# eit_passive_filter.net
KiCad netlist of a schematic drawn in EAGLE
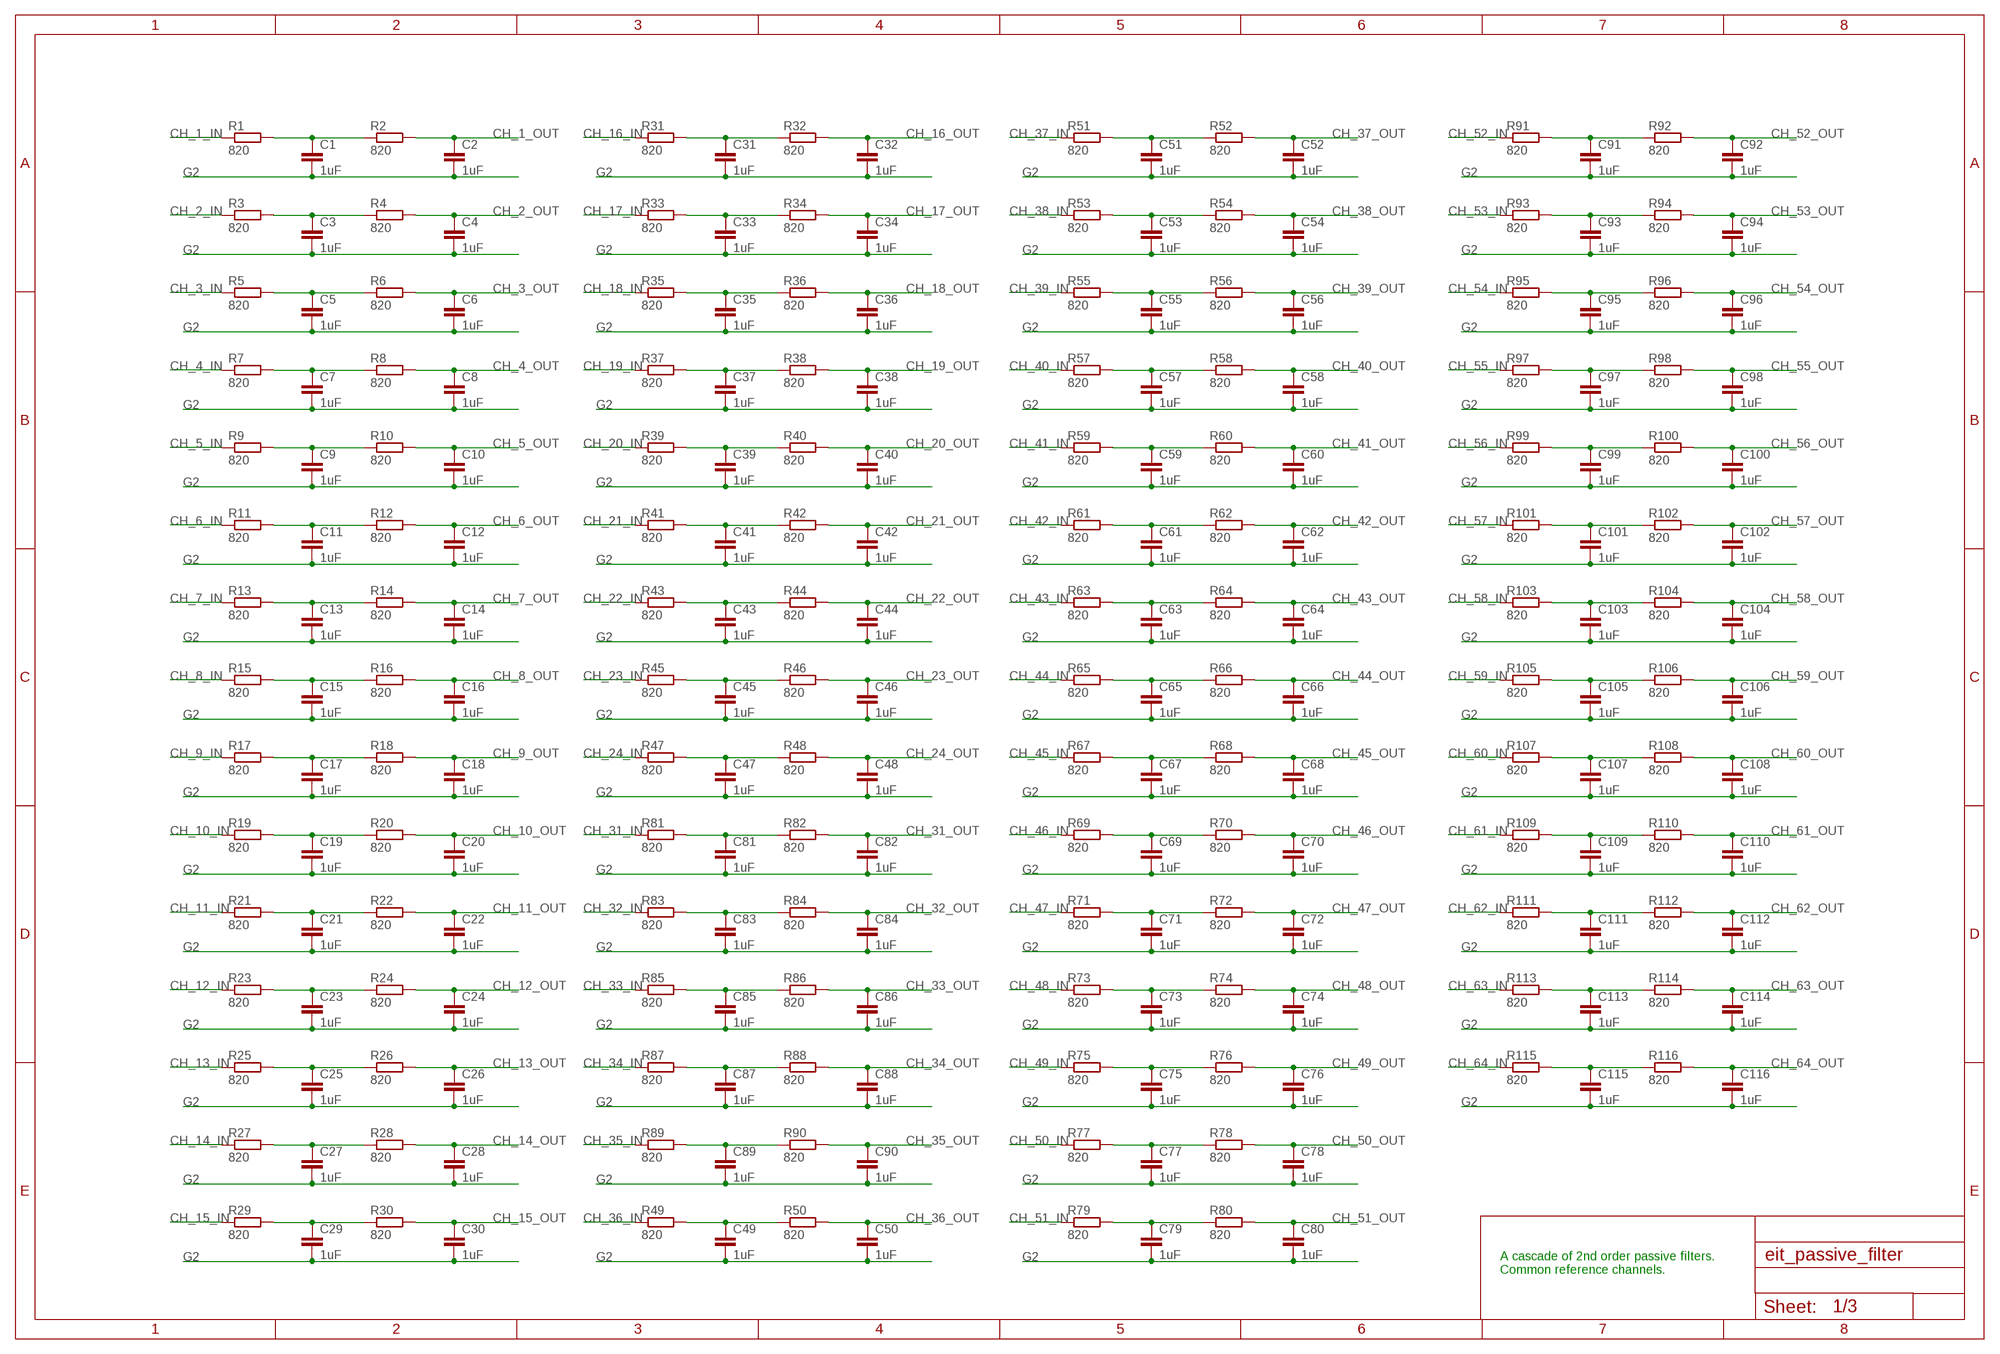
[diagram p0: schematic, sheet 1]
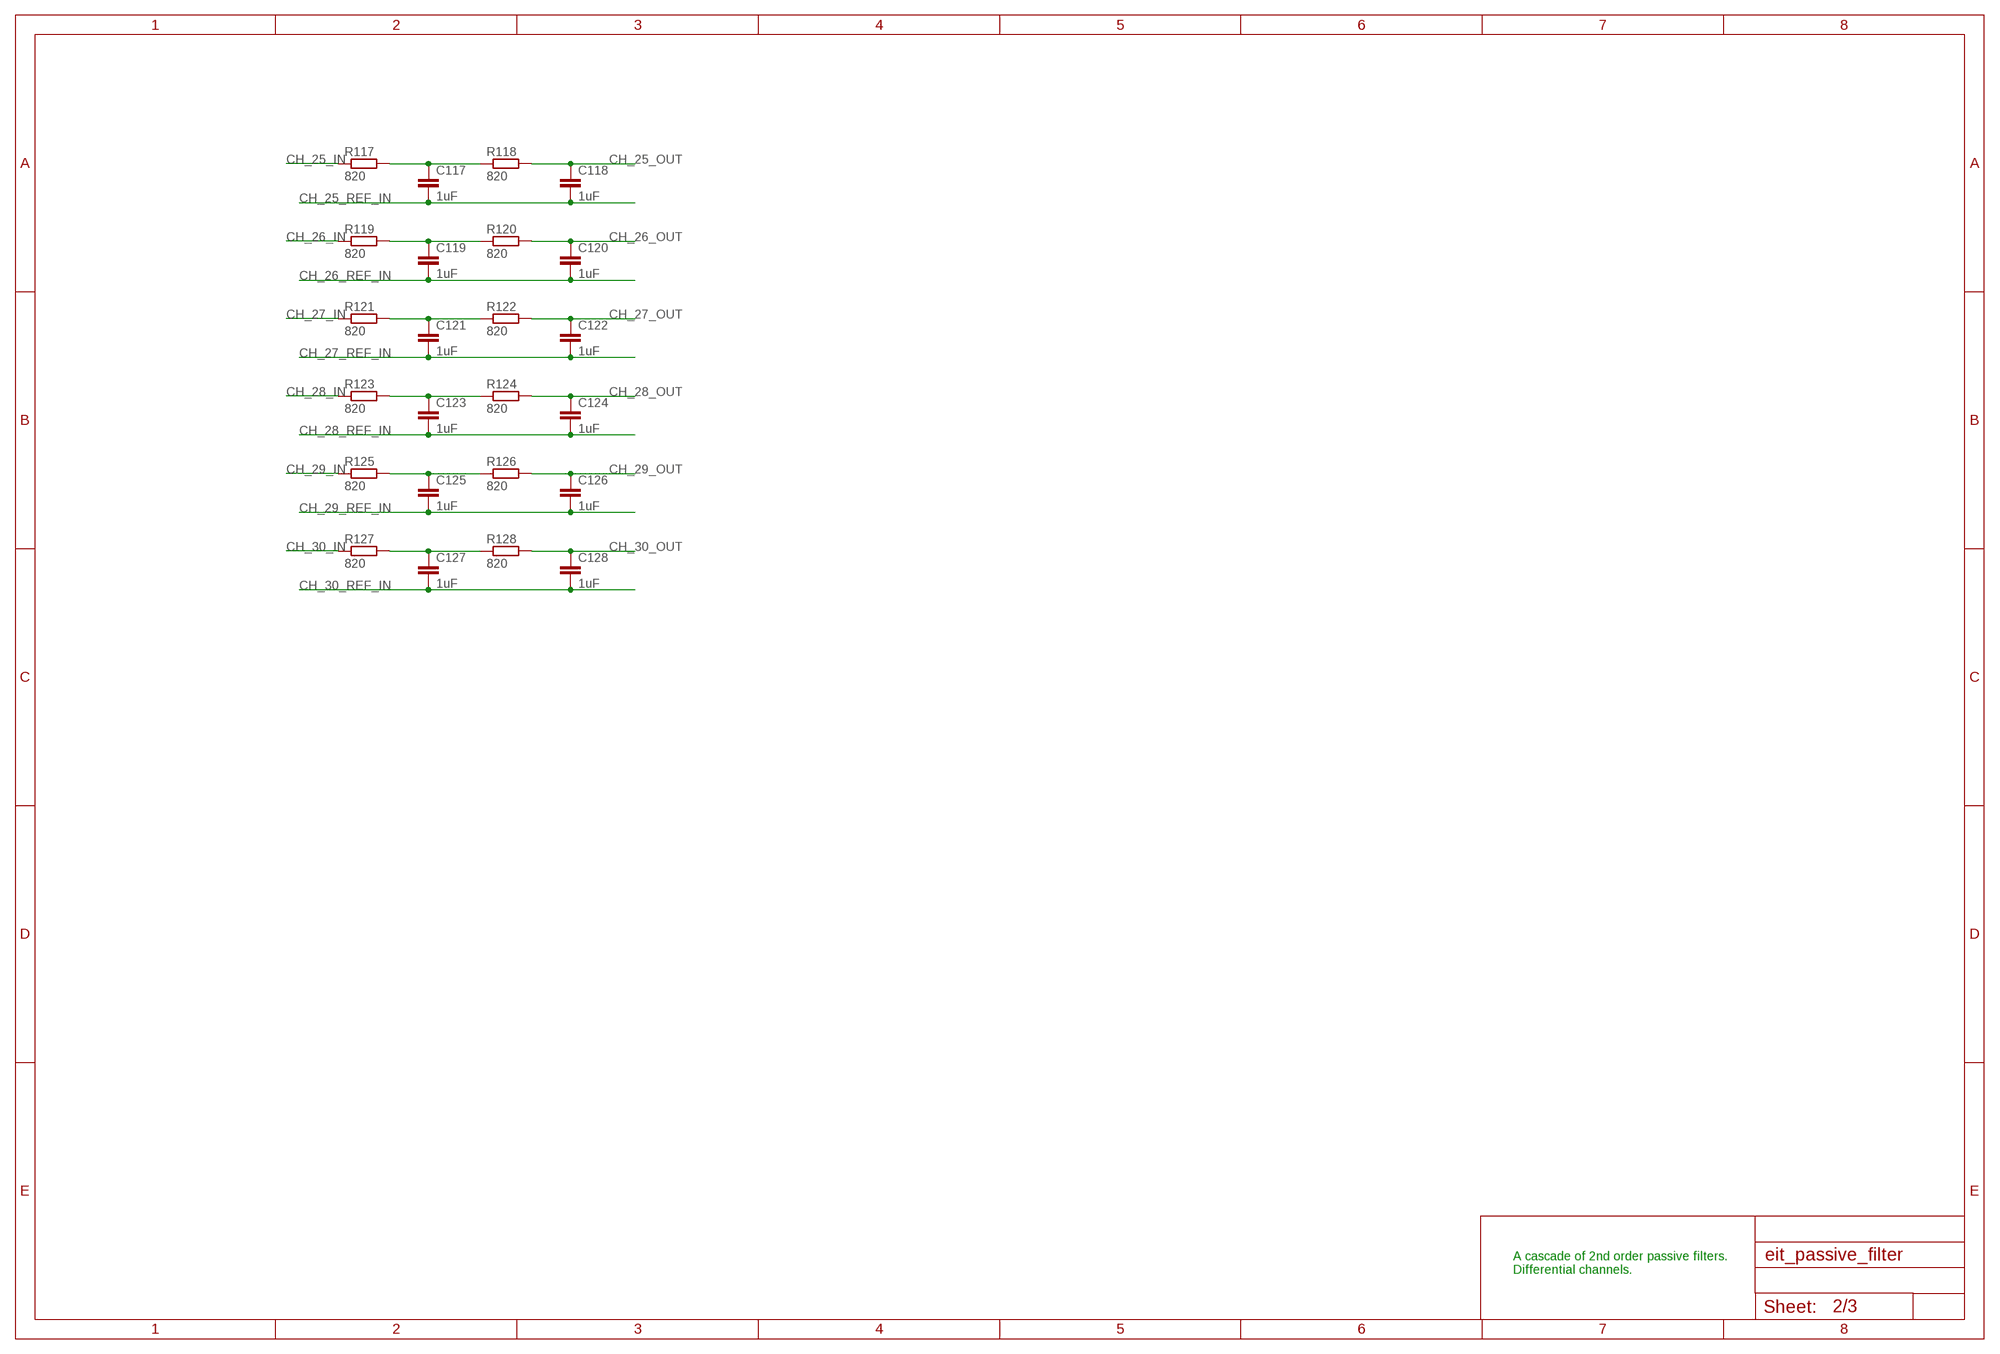
[diagram p1: schematic, sheet 2]
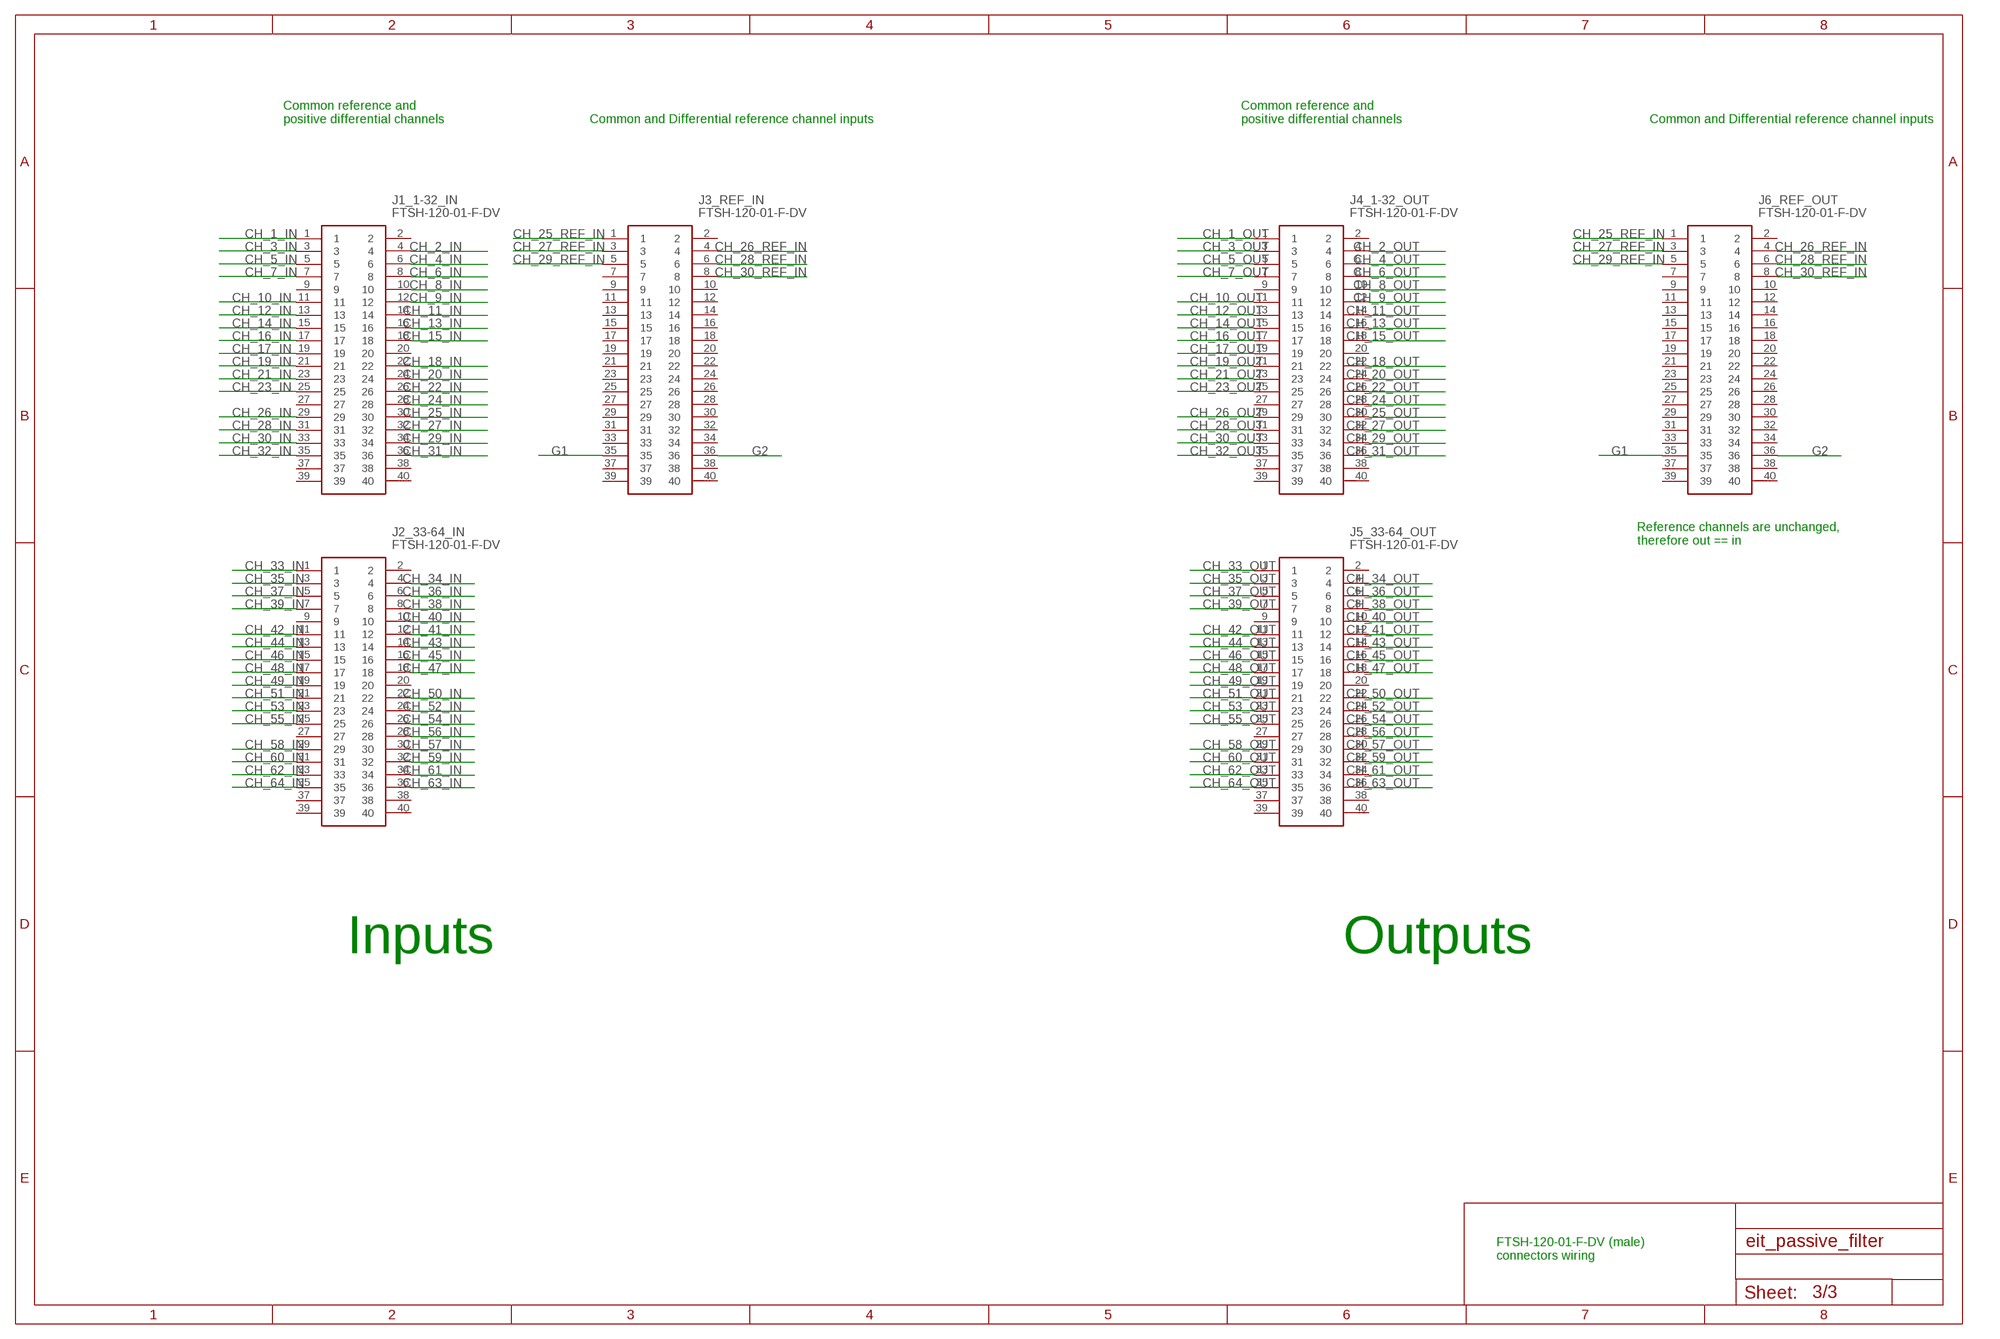
[diagram p2: schematic, sheet 3]

(export (version "E")
  (design (tool "Eeschema 10.0.6"))
  (components
    (comp (ref "J1_1-32_IN")
      (value "FTSH-120-01-F-DV")
      (footprint "eagle-import:FTSH-120-XX-YYY-DV")
      (fields (field (name "MOUSER_PART_NUMBER") "200-FTSH12001FDV"))
      (libsource (lib "eagle-import") (part "FTSH-120-01-F-DV"))
    )
    (comp (ref "J2_33-64_IN")
      (value "FTSH-120-01-F-DV")
      (footprint "eagle-import:FTSH-120-XX-YYY-DV")
      (fields (field (name "MOUSER_PART_NUMBER") "200-FTSH12001FDV"))
      (libsource (lib "eagle-import") (part "FTSH-120-01-F-DV"))
    )
    (comp (ref "J3_REF_IN")
      (value "FTSH-120-01-F-DV")
      (footprint "eagle-import:FTSH-120-XX-YYY-DV")
      (fields (field (name "MOUSER_PART_NUMBER") "200-FTSH12001FDV"))
      (libsource (lib "eagle-import") (part "FTSH-120-01-F-DV"))
    )
    (comp (ref "J4_1-32_OUT")
      (value "FTSH-120-01-F-DV")
      (footprint "eagle-import:FTSH-120-XX-YYY-DV")
      (fields (field (name "MOUSER_PART_NUMBER") "200-FTSH12001FDV"))
      (libsource (lib "eagle-import") (part "FTSH-120-01-F-DV"))
    )
    (comp (ref "J5_33-64_OUT")
      (value "FTSH-120-01-F-DV")
      (footprint "eagle-import:FTSH-120-XX-YYY-DV")
      (fields (field (name "MOUSER_PART_NUMBER") "200-FTSH12001FDV"))
      (libsource (lib "eagle-import") (part "FTSH-120-01-F-DV"))
    )
    (comp (ref "J6_REF_OUT")
      (value "FTSH-120-01-F-DV")
      (footprint "eagle-import:FTSH-120-XX-YYY-DV")
      (fields (field (name "MOUSER_PART_NUMBER") "200-FTSH12001FDV"))
      (libsource (lib "eagle-import") (part "FTSH-120-01-F-DV"))
    )
    (comp (ref "C117")
      (value "1uF")
      (footprint "eagle-import:C0402")
      (libsource (lib "eagle-import") (part "C-EUC0402"))
    )
    (comp (ref "C118")
      (value "1uF")
      (footprint "eagle-import:C0402")
      (libsource (lib "eagle-import") (part "C-EUC0402"))
    )
    (comp (ref "C119")
      (value "1uF")
      (footprint "eagle-import:C0402")
      (libsource (lib "eagle-import") (part "C-EUC0402"))
    )
    (comp (ref "C120")
      (value "1uF")
      (footprint "eagle-import:C0402")
      (libsource (lib "eagle-import") (part "C-EUC0402"))
    )
    (comp (ref "C121")
      (value "1uF")
      (footprint "eagle-import:C0402")
      (libsource (lib "eagle-import") (part "C-EUC0402"))
    )
    (comp (ref "C122")
      (value "1uF")
      (footprint "eagle-import:C0402")
      (libsource (lib "eagle-import") (part "C-EUC0402"))
    )
    (comp (ref "C123")
      (value "1uF")
      (footprint "eagle-import:C0402")
      (libsource (lib "eagle-import") (part "C-EUC0402"))
    )
    (comp (ref "C124")
      (value "1uF")
      (footprint "eagle-import:C0402")
      (libsource (lib "eagle-import") (part "C-EUC0402"))
    )
    (comp (ref "C125")
      (value "1uF")
      (footprint "eagle-import:C0402")
      (libsource (lib "eagle-import") (part "C-EUC0402"))
    )
    (comp (ref "C126")
      (value "1uF")
      (footprint "eagle-import:C0402")
      (libsource (lib "eagle-import") (part "C-EUC0402"))
    )
    (comp (ref "C127")
      (value "1uF")
      (footprint "eagle-import:C0402")
      (libsource (lib "eagle-import") (part "C-EUC0402"))
    )
    (comp (ref "C128")
      (value "1uF")
      (footprint "eagle-import:C0402")
      (libsource (lib "eagle-import") (part "C-EUC0402"))
    )
    (comp (ref "R117")
      (value "820")
      (footprint "eagle-import:R0402")
      (libsource (lib "eagle-import") (part "R-EU_R0402"))
    )
    (comp (ref "R118")
      (value "820")
      (footprint "eagle-import:R0402")
      (libsource (lib "eagle-import") (part "R-EU_R0402"))
    )
    (comp (ref "R119")
      (value "820")
      (footprint "eagle-import:R0402")
      (libsource (lib "eagle-import") (part "R-EU_R0402"))
    )
    (comp (ref "R120")
      (value "820")
      (footprint "eagle-import:R0402")
      (libsource (lib "eagle-import") (part "R-EU_R0402"))
    )
    (comp (ref "R121")
      (value "820")
      (footprint "eagle-import:R0402")
      (libsource (lib "eagle-import") (part "R-EU_R0402"))
    )
    (comp (ref "R122")
      (value "820")
      (footprint "eagle-import:R0402")
      (libsource (lib "eagle-import") (part "R-EU_R0402"))
    )
    (comp (ref "R123")
      (value "820")
      (footprint "eagle-import:R0402")
      (libsource (lib "eagle-import") (part "R-EU_R0402"))
    )
    (comp (ref "R124")
      (value "820")
      (footprint "eagle-import:R0402")
      (libsource (lib "eagle-import") (part "R-EU_R0402"))
    )
    (comp (ref "R125")
      (value "820")
      (footprint "eagle-import:R0402")
      (libsource (lib "eagle-import") (part "R-EU_R0402"))
    )
    (comp (ref "R126")
      (value "820")
      (footprint "eagle-import:R0402")
      (libsource (lib "eagle-import") (part "R-EU_R0402"))
    )
    (comp (ref "R127")
      (value "820")
      (footprint "eagle-import:R0402")
      (libsource (lib "eagle-import") (part "R-EU_R0402"))
    )
    (comp (ref "R128")
      (value "820")
      (footprint "eagle-import:R0402")
      (libsource (lib "eagle-import") (part "R-EU_R0402"))
    )
    (comp (ref "C1")
      (value "1uF")
      (footprint "eagle-import:C0402")
      (libsource (lib "eagle-import") (part "C-EUC0402"))
    )
    (comp (ref "C2")
      (value "1uF")
      (footprint "eagle-import:C0402")
      (libsource (lib "eagle-import") (part "C-EUC0402"))
    )
    (comp (ref "C3")
      (value "1uF")
      (footprint "eagle-import:C0402")
      (libsource (lib "eagle-import") (part "C-EUC0402"))
    )
    (comp (ref "C4")
      (value "1uF")
      (footprint "eagle-import:C0402")
      (libsource (lib "eagle-import") (part "C-EUC0402"))
    )
    (comp (ref "C5")
      (value "1uF")
      (footprint "eagle-import:C0402")
      (libsource (lib "eagle-import") (part "C-EUC0402"))
    )
    (comp (ref "C6")
      (value "1uF")
      (footprint "eagle-import:C0402")
      (libsource (lib "eagle-import") (part "C-EUC0402"))
    )
    (comp (ref "C7")
      (value "1uF")
      (footprint "eagle-import:C0402")
      (libsource (lib "eagle-import") (part "C-EUC0402"))
    )
    (comp (ref "C8")
      (value "1uF")
      (footprint "eagle-import:C0402")
      (libsource (lib "eagle-import") (part "C-EUC0402"))
    )
    (comp (ref "C9")
      (value "1uF")
      (footprint "eagle-import:C0402")
      (libsource (lib "eagle-import") (part "C-EUC0402"))
    )
    (comp (ref "C10")
      (value "1uF")
      (footprint "eagle-import:C0402")
      (libsource (lib "eagle-import") (part "C-EUC0402"))
    )
    (comp (ref "C11")
      (value "1uF")
      (footprint "eagle-import:C0402")
      (libsource (lib "eagle-import") (part "C-EUC0402"))
    )
    (comp (ref "C12")
      (value "1uF")
      (footprint "eagle-import:C0402")
      (libsource (lib "eagle-import") (part "C-EUC0402"))
    )
    (comp (ref "C13")
      (value "1uF")
      (footprint "eagle-import:C0402")
      (libsource (lib "eagle-import") (part "C-EUC0402"))
    )
    (comp (ref "C14")
      (value "1uF")
      (footprint "eagle-import:C0402")
      (libsource (lib "eagle-import") (part "C-EUC0402"))
    )
    (comp (ref "C15")
      (value "1uF")
      (footprint "eagle-import:C0402")
      (libsource (lib "eagle-import") (part "C-EUC0402"))
    )
    (comp (ref "C16")
      (value "1uF")
      (footprint "eagle-import:C0402")
      (libsource (lib "eagle-import") (part "C-EUC0402"))
    )
    (comp (ref "C17")
      (value "1uF")
      (footprint "eagle-import:C0402")
      (libsource (lib "eagle-import") (part "C-EUC0402"))
    )
    (comp (ref "C18")
      (value "1uF")
      (footprint "eagle-import:C0402")
      (libsource (lib "eagle-import") (part "C-EUC0402"))
    )
    (comp (ref "C19")
      (value "1uF")
      (footprint "eagle-import:C0402")
      (libsource (lib "eagle-import") (part "C-EUC0402"))
    )
    (comp (ref "C20")
      (value "1uF")
      (footprint "eagle-import:C0402")
      (libsource (lib "eagle-import") (part "C-EUC0402"))
    )
    (comp (ref "C21")
      (value "1uF")
      (footprint "eagle-import:C0402")
      (libsource (lib "eagle-import") (part "C-EUC0402"))
    )
    (comp (ref "C22")
      (value "1uF")
      (footprint "eagle-import:C0402")
      (libsource (lib "eagle-import") (part "C-EUC0402"))
    )
    (comp (ref "C23")
      (value "1uF")
      (footprint "eagle-import:C0402")
      (libsource (lib "eagle-import") (part "C-EUC0402"))
    )
    (comp (ref "C24")
      (value "1uF")
      (footprint "eagle-import:C0402")
      (libsource (lib "eagle-import") (part "C-EUC0402"))
    )
    (comp (ref "C25")
      (value "1uF")
      (footprint "eagle-import:C0402")
      (libsource (lib "eagle-import") (part "C-EUC0402"))
    )
    (comp (ref "C26")
      (value "1uF")
      (footprint "eagle-import:C0402")
      (libsource (lib "eagle-import") (part "C-EUC0402"))
    )
    (comp (ref "C27")
      (value "1uF")
      (footprint "eagle-import:C0402")
      (libsource (lib "eagle-import") (part "C-EUC0402"))
    )
    (comp (ref "C28")
      (value "1uF")
      (footprint "eagle-import:C0402")
      (libsource (lib "eagle-import") (part "C-EUC0402"))
    )
    (comp (ref "C29")
      (value "1uF")
      (footprint "eagle-import:C0402")
      (libsource (lib "eagle-import") (part "C-EUC0402"))
    )
    (comp (ref "C30")
      (value "1uF")
      (footprint "eagle-import:C0402")
      (libsource (lib "eagle-import") (part "C-EUC0402"))
    )
    (comp (ref "C31")
      (value "1uF")
      (footprint "eagle-import:C0402")
      (libsource (lib "eagle-import") (part "C-EUC0402"))
    )
    (comp (ref "C32")
      (value "1uF")
      (footprint "eagle-import:C0402")
      (libsource (lib "eagle-import") (part "C-EUC0402"))
    )
    (comp (ref "C33")
      (value "1uF")
      (footprint "eagle-import:C0402")
      (libsource (lib "eagle-import") (part "C-EUC0402"))
    )
    (comp (ref "C34")
      (value "1uF")
      (footprint "eagle-import:C0402")
      (libsource (lib "eagle-import") (part "C-EUC0402"))
    )
    (comp (ref "C35")
      (value "1uF")
      (footprint "eagle-import:C0402")
      (libsource (lib "eagle-import") (part "C-EUC0402"))
    )
    (comp (ref "C36")
      (value "1uF")
      (footprint "eagle-import:C0402")
      (libsource (lib "eagle-import") (part "C-EUC0402"))
    )
    (comp (ref "C37")
      (value "1uF")
      (footprint "eagle-import:C0402")
      (libsource (lib "eagle-import") (part "C-EUC0402"))
    )
    (comp (ref "C38")
      (value "1uF")
      (footprint "eagle-import:C0402")
      (libsource (lib "eagle-import") (part "C-EUC0402"))
    )
    (comp (ref "C39")
      (value "1uF")
      (footprint "eagle-import:C0402")
      (libsource (lib "eagle-import") (part "C-EUC0402"))
    )
    (comp (ref "C40")
      (value "1uF")
      (footprint "eagle-import:C0402")
      (libsource (lib "eagle-import") (part "C-EUC0402"))
    )
    (comp (ref "C41")
      (value "1uF")
      (footprint "eagle-import:C0402")
      (libsource (lib "eagle-import") (part "C-EUC0402"))
    )
    (comp (ref "C42")
      (value "1uF")
      (footprint "eagle-import:C0402")
      (libsource (lib "eagle-import") (part "C-EUC0402"))
    )
    (comp (ref "C43")
      (value "1uF")
      (footprint "eagle-import:C0402")
      (libsource (lib "eagle-import") (part "C-EUC0402"))
    )
    (comp (ref "C44")
      (value "1uF")
      (footprint "eagle-import:C0402")
      (libsource (lib "eagle-import") (part "C-EUC0402"))
    )
    (comp (ref "C45")
      (value "1uF")
      (footprint "eagle-import:C0402")
      (libsource (lib "eagle-import") (part "C-EUC0402"))
    )
    (comp (ref "C46")
      (value "1uF")
      (footprint "eagle-import:C0402")
      (libsource (lib "eagle-import") (part "C-EUC0402"))
    )
    (comp (ref "C47")
      (value "1uF")
      (footprint "eagle-import:C0402")
      (libsource (lib "eagle-import") (part "C-EUC0402"))
    )
    (comp (ref "C48")
      (value "1uF")
      (footprint "eagle-import:C0402")
      (libsource (lib "eagle-import") (part "C-EUC0402"))
    )
    (comp (ref "C49")
      (value "1uF")
      (footprint "eagle-import:C0402")
      (libsource (lib "eagle-import") (part "C-EUC0402"))
    )
    (comp (ref "C50")
      (value "1uF")
      (footprint "eagle-import:C0402")
      (libsource (lib "eagle-import") (part "C-EUC0402"))
    )
    (comp (ref "C51")
      (value "1uF")
      (footprint "eagle-import:C0402")
      (libsource (lib "eagle-import") (part "C-EUC0402"))
    )
    (comp (ref "C52")
      (value "1uF")
      (footprint "eagle-import:C0402")
      (libsource (lib "eagle-import") (part "C-EUC0402"))
    )
    (comp (ref "C53")
      (value "1uF")
      (footprint "eagle-import:C0402")
      (libsource (lib "eagle-import") (part "C-EUC0402"))
    )
    (comp (ref "C54")
      (value "1uF")
      (footprint "eagle-import:C0402")
      (libsource (lib "eagle-import") (part "C-EUC0402"))
    )
    (comp (ref "C55")
      (value "1uF")
      (footprint "eagle-import:C0402")
      (libsource (lib "eagle-import") (part "C-EUC0402"))
    )
    (comp (ref "C56")
      (value "1uF")
      (footprint "eagle-import:C0402")
      (libsource (lib "eagle-import") (part "C-EUC0402"))
    )
    (comp (ref "C57")
      (value "1uF")
      (footprint "eagle-import:C0402")
      (libsource (lib "eagle-import") (part "C-EUC0402"))
    )
    (comp (ref "C58")
      (value "1uF")
      (footprint "eagle-import:C0402")
      (libsource (lib "eagle-import") (part "C-EUC0402"))
    )
    (comp (ref "C59")
      (value "1uF")
      (footprint "eagle-import:C0402")
      (libsource (lib "eagle-import") (part "C-EUC0402"))
    )
    (comp (ref "C60")
      (value "1uF")
      (footprint "eagle-import:C0402")
      (libsource (lib "eagle-import") (part "C-EUC0402"))
    )
    (comp (ref "C61")
      (value "1uF")
      (footprint "eagle-import:C0402")
      (libsource (lib "eagle-import") (part "C-EUC0402"))
    )
    (comp (ref "C62")
      (value "1uF")
      (footprint "eagle-import:C0402")
      (libsource (lib "eagle-import") (part "C-EUC0402"))
    )
    (comp (ref "C63")
      (value "1uF")
      (footprint "eagle-import:C0402")
      (libsource (lib "eagle-import") (part "C-EUC0402"))
    )
    (comp (ref "C64")
      (value "1uF")
      (footprint "eagle-import:C0402")
      (libsource (lib "eagle-import") (part "C-EUC0402"))
    )
    (comp (ref "C65")
      (value "1uF")
      (footprint "eagle-import:C0402")
      (libsource (lib "eagle-import") (part "C-EUC0402"))
    )
    (comp (ref "C66")
      (value "1uF")
      (footprint "eagle-import:C0402")
      (libsource (lib "eagle-import") (part "C-EUC0402"))
    )
    (comp (ref "C67")
      (value "1uF")
      (footprint "eagle-import:C0402")
      (libsource (lib "eagle-import") (part "C-EUC0402"))
    )
    (comp (ref "C68")
      (value "1uF")
      (footprint "eagle-import:C0402")
      (libsource (lib "eagle-import") (part "C-EUC0402"))
    )
    (comp (ref "C69")
      (value "1uF")
      (footprint "eagle-import:C0402")
      (libsource (lib "eagle-import") (part "C-EUC0402"))
    )
    (comp (ref "C70")
      (value "1uF")
      (footprint "eagle-import:C0402")
      (libsource (lib "eagle-import") (part "C-EUC0402"))
    )
    (comp (ref "C71")
      (value "1uF")
      (footprint "eagle-import:C0402")
      (libsource (lib "eagle-import") (part "C-EUC0402"))
    )
    (comp (ref "C72")
      (value "1uF")
      (footprint "eagle-import:C0402")
      (libsource (lib "eagle-import") (part "C-EUC0402"))
    )
    (comp (ref "C73")
      (value "1uF")
      (footprint "eagle-import:C0402")
      (libsource (lib "eagle-import") (part "C-EUC0402"))
    )
    (comp (ref "C74")
      (value "1uF")
      (footprint "eagle-import:C0402")
      (libsource (lib "eagle-import") (part "C-EUC0402"))
    )
    (comp (ref "C75")
      (value "1uF")
      (footprint "eagle-import:C0402")
      (libsource (lib "eagle-import") (part "C-EUC0402"))
    )
    (comp (ref "C76")
      (value "1uF")
      (footprint "eagle-import:C0402")
      (libsource (lib "eagle-import") (part "C-EUC0402"))
    )
    (comp (ref "C77")
      (value "1uF")
      (footprint "eagle-import:C0402")
      (libsource (lib "eagle-import") (part "C-EUC0402"))
    )
    (comp (ref "C78")
      (value "1uF")
      (footprint "eagle-import:C0402")
      (libsource (lib "eagle-import") (part "C-EUC0402"))
    )
    (comp (ref "C79")
      (value "1uF")
      (footprint "eagle-import:C0402")
      (libsource (lib "eagle-import") (part "C-EUC0402"))
    )
    (comp (ref "C80")
      (value "1uF")
      (footprint "eagle-import:C0402")
      (libsource (lib "eagle-import") (part "C-EUC0402"))
    )
    (comp (ref "C81")
      (value "1uF")
      (footprint "eagle-import:C0402")
      (libsource (lib "eagle-import") (part "C-EUC0402"))
    )
    (comp (ref "C82")
      (value "1uF")
      (footprint "eagle-import:C0402")
      (libsource (lib "eagle-import") (part "C-EUC0402"))
    )
    (comp (ref "C83")
      (value "1uF")
      (footprint "eagle-import:C0402")
      (libsource (lib "eagle-import") (part "C-EUC0402"))
    )
    (comp (ref "C84")
      (value "1uF")
      (footprint "eagle-import:C0402")
      (libsource (lib "eagle-import") (part "C-EUC0402"))
    )
    (comp (ref "C85")
      (value "1uF")
      (footprint "eagle-import:C0402")
      (libsource (lib "eagle-import") (part "C-EUC0402"))
    )
    (comp (ref "C86")
      (value "1uF")
      (footprint "eagle-import:C0402")
      (libsource (lib "eagle-import") (part "C-EUC0402"))
    )
    (comp (ref "C87")
      (value "1uF")
      (footprint "eagle-import:C0402")
      (libsource (lib "eagle-import") (part "C-EUC0402"))
    )
    (comp (ref "C88")
      (value "1uF")
      (footprint "eagle-import:C0402")
      (libsource (lib "eagle-import") (part "C-EUC0402"))
    )
    (comp (ref "C89")
      (value "1uF")
      (footprint "eagle-import:C0402")
      (libsource (lib "eagle-import") (part "C-EUC0402"))
    )
    (comp (ref "C90")
      (value "1uF")
      (footprint "eagle-import:C0402")
      (libsource (lib "eagle-import") (part "C-EUC0402"))
    )
    (comp (ref "C91")
      (value "1uF")
      (footprint "eagle-import:C0402")
      (libsource (lib "eagle-import") (part "C-EUC0402"))
    )
    (comp (ref "C92")
      (value "1uF")
      (footprint "eagle-import:C0402")
      (libsource (lib "eagle-import") (part "C-EUC0402"))
    )
    (comp (ref "C93")
      (value "1uF")
      (footprint "eagle-import:C0402")
      (libsource (lib "eagle-import") (part "C-EUC0402"))
    )
    (comp (ref "C94")
      (value "1uF")
      (footprint "eagle-import:C0402")
      (libsource (lib "eagle-import") (part "C-EUC0402"))
    )
    (comp (ref "C95")
      (value "1uF")
      (footprint "eagle-import:C0402")
      (libsource (lib "eagle-import") (part "C-EUC0402"))
    )
    (comp (ref "C96")
      (value "1uF")
      (footprint "eagle-import:C0402")
      (libsource (lib "eagle-import") (part "C-EUC0402"))
    )
    (comp (ref "C97")
      (value "1uF")
      (footprint "eagle-import:C0402")
      (libsource (lib "eagle-import") (part "C-EUC0402"))
    )
    (comp (ref "C98")
      (value "1uF")
      (footprint "eagle-import:C0402")
      (libsource (lib "eagle-import") (part "C-EUC0402"))
    )
    (comp (ref "C99")
      (value "1uF")
      (footprint "eagle-import:C0402")
      (libsource (lib "eagle-import") (part "C-EUC0402"))
    )
    (comp (ref "C100")
      (value "1uF")
      (footprint "eagle-import:C0402")
      (libsource (lib "eagle-import") (part "C-EUC0402"))
    )
    (comp (ref "C101")
      (value "1uF")
      (footprint "eagle-import:C0402")
      (libsource (lib "eagle-import") (part "C-EUC0402"))
    )
    (comp (ref "C102")
      (value "1uF")
      (footprint "eagle-import:C0402")
      (libsource (lib "eagle-import") (part "C-EUC0402"))
    )
    (comp (ref "C103")
      (value "1uF")
      (footprint "eagle-import:C0402")
      (libsource (lib "eagle-import") (part "C-EUC0402"))
    )
    (comp (ref "C104")
      (value "1uF")
      (footprint "eagle-import:C0402")
      (libsource (lib "eagle-import") (part "C-EUC0402"))
    )
    (comp (ref "C105")
      (value "1uF")
      (footprint "eagle-import:C0402")
      (libsource (lib "eagle-import") (part "C-EUC0402"))
    )
    (comp (ref "C106")
      (value "1uF")
      (footprint "eagle-import:C0402")
      (libsource (lib "eagle-import") (part "C-EUC0402"))
    )
    (comp (ref "C107")
      (value "1uF")
      (footprint "eagle-import:C0402")
      (libsource (lib "eagle-import") (part "C-EUC0402"))
    )
    (comp (ref "C108")
      (value "1uF")
      (footprint "eagle-import:C0402")
      (libsource (lib "eagle-import") (part "C-EUC0402"))
    )
    (comp (ref "C109")
      (value "1uF")
      (footprint "eagle-import:C0402")
      (libsource (lib "eagle-import") (part "C-EUC0402"))
    )
    (comp (ref "C110")
      (value "1uF")
      (footprint "eagle-import:C0402")
      (libsource (lib "eagle-import") (part "C-EUC0402"))
    )
    (comp (ref "C111")
      (value "1uF")
      (footprint "eagle-import:C0402")
      (libsource (lib "eagle-import") (part "C-EUC0402"))
    )
    (comp (ref "C112")
      (value "1uF")
      (footprint "eagle-import:C0402")
      (libsource (lib "eagle-import") (part "C-EUC0402"))
    )
    (comp (ref "C113")
      (value "1uF")
      (footprint "eagle-import:C0402")
      (libsource (lib "eagle-import") (part "C-EUC0402"))
    )
    (comp (ref "C114")
      (value "1uF")
      (footprint "eagle-import:C0402")
      (libsource (lib "eagle-import") (part "C-EUC0402"))
    )
    (comp (ref "C115")
      (value "1uF")
      (footprint "eagle-import:C0402")
      (libsource (lib "eagle-import") (part "C-EUC0402"))
    )
    (comp (ref "C116")
      (value "1uF")
      (footprint "eagle-import:C0402")
      (libsource (lib "eagle-import") (part "C-EUC0402"))
    )
    (comp (ref "R1")
      (value "820")
      (footprint "eagle-import:R0402")
      (libsource (lib "eagle-import") (part "R-EU_R0402"))
    )
    (comp (ref "R2")
      (value "820")
      (footprint "eagle-import:R0402")
      (libsource (lib "eagle-import") (part "R-EU_R0402"))
    )
    (comp (ref "R3")
      (value "820")
      (footprint "eagle-import:R0402")
      (libsource (lib "eagle-import") (part "R-EU_R0402"))
    )
    (comp (ref "R4")
      (value "820")
      (footprint "eagle-import:R0402")
      (libsource (lib "eagle-import") (part "R-EU_R0402"))
    )
    (comp (ref "R5")
      (value "820")
      (footprint "eagle-import:R0402")
      (libsource (lib "eagle-import") (part "R-EU_R0402"))
    )
    (comp (ref "R6")
      (value "820")
      (footprint "eagle-import:R0402")
      (libsource (lib "eagle-import") (part "R-EU_R0402"))
    )
    (comp (ref "R7")
      (value "820")
      (footprint "eagle-import:R0402")
      (libsource (lib "eagle-import") (part "R-EU_R0402"))
    )
    (comp (ref "R8")
      (value "820")
      (footprint "eagle-import:R0402")
      (libsource (lib "eagle-import") (part "R-EU_R0402"))
    )
    (comp (ref "R9")
      (value "820")
      (footprint "eagle-import:R0402")
      (libsource (lib "eagle-import") (part "R-EU_R0402"))
    )
    (comp (ref "R10")
      (value "820")
      (footprint "eagle-import:R0402")
      (libsource (lib "eagle-import") (part "R-EU_R0402"))
    )
    (comp (ref "R11")
      (value "820")
      (footprint "eagle-import:R0402")
      (libsource (lib "eagle-import") (part "R-EU_R0402"))
    )
    (comp (ref "R12")
      (value "820")
      (footprint "eagle-import:R0402")
      (libsource (lib "eagle-import") (part "R-EU_R0402"))
    )
    (comp (ref "R13")
      (value "820")
      (footprint "eagle-import:R0402")
      (libsource (lib "eagle-import") (part "R-EU_R0402"))
    )
    (comp (ref "R14")
      (value "820")
      (footprint "eagle-import:R0402")
      (libsource (lib "eagle-import") (part "R-EU_R0402"))
    )
    (comp (ref "R15")
      (value "820")
      (footprint "eagle-import:R0402")
      (libsource (lib "eagle-import") (part "R-EU_R0402"))
    )
    (comp (ref "R16")
      (value "820")
      (footprint "eagle-import:R0402")
      (libsource (lib "eagle-import") (part "R-EU_R0402"))
    )
    (comp (ref "R17")
      (value "820")
      (footprint "eagle-import:R0402")
      (libsource (lib "eagle-import") (part "R-EU_R0402"))
    )
    (comp (ref "R18")
      (value "820")
      (footprint "eagle-import:R0402")
      (libsource (lib "eagle-import") (part "R-EU_R0402"))
    )
    (comp (ref "R19")
      (value "820")
      (footprint "eagle-import:R0402")
      (libsource (lib "eagle-import") (part "R-EU_R0402"))
    )
    (comp (ref "R20")
      (value "820")
      (footprint "eagle-import:R0402")
      (libsource (lib "eagle-import") (part "R-EU_R0402"))
    )
    (comp (ref "R21")
      (value "820")
      (footprint "eagle-import:R0402")
      (libsource (lib "eagle-import") (part "R-EU_R0402"))
    )
    (comp (ref "R22")
      (value "820")
      (footprint "eagle-import:R0402")
      (libsource (lib "eagle-import") (part "R-EU_R0402"))
    )
    (comp (ref "R23")
      (value "820")
      (footprint "eagle-import:R0402")
      (libsource (lib "eagle-import") (part "R-EU_R0402"))
    )
    (comp (ref "R24")
      (value "820")
      (footprint "eagle-import:R0402")
      (libsource (lib "eagle-import") (part "R-EU_R0402"))
    )
    (comp (ref "R25")
      (value "820")
      (footprint "eagle-import:R0402")
      (libsource (lib "eagle-import") (part "R-EU_R0402"))
    )
    (comp (ref "R26")
      (value "820")
      (footprint "eagle-import:R0402")
      (libsource (lib "eagle-import") (part "R-EU_R0402"))
    )
    (comp (ref "R27")
      (value "820")
      (footprint "eagle-import:R0402")
      (libsource (lib "eagle-import") (part "R-EU_R0402"))
    )
    (comp (ref "R28")
      (value "820")
      (footprint "eagle-import:R0402")
      (libsource (lib "eagle-import") (part "R-EU_R0402"))
    )
    (comp (ref "R29")
      (value "820")
      (footprint "eagle-import:R0402")
      (libsource (lib "eagle-import") (part "R-EU_R0402"))
    )
    (comp (ref "R30")
      (value "820")
      (footprint "eagle-import:R0402")
      (libsource (lib "eagle-import") (part "R-EU_R0402"))
    )
    (comp (ref "R31")
      (value "820")
      (footprint "eagle-import:R0402")
      (libsource (lib "eagle-import") (part "R-EU_R0402"))
    )
    (comp (ref "R32")
      (value "820")
      (footprint "eagle-import:R0402")
      (libsource (lib "eagle-import") (part "R-EU_R0402"))
    )
    (comp (ref "R33")
      (value "820")
      (footprint "eagle-import:R0402")
      (libsource (lib "eagle-import") (part "R-EU_R0402"))
    )
    (comp (ref "R34")
      (value "820")
      (footprint "eagle-import:R0402")
      (libsource (lib "eagle-import") (part "R-EU_R0402"))
    )
    (comp (ref "R35")
      (value "820")
      (footprint "eagle-import:R0402")
      (libsource (lib "eagle-import") (part "R-EU_R0402"))
    )
    (comp (ref "R36")
      (value "820")
      (footprint "eagle-import:R0402")
      (libsource (lib "eagle-import") (part "R-EU_R0402"))
    )
    (comp (ref "R37")
      (value "820")
      (footprint "eagle-import:R0402")
      (libsource (lib "eagle-import") (part "R-EU_R0402"))
    )
    (comp (ref "R38")
      (value "820")
      (footprint "eagle-import:R0402")
      (libsource (lib "eagle-import") (part "R-EU_R0402"))
    )
    (comp (ref "R39")
      (value "820")
      (footprint "eagle-import:R0402")
      (libsource (lib "eagle-import") (part "R-EU_R0402"))
    )
    (comp (ref "R40")
      (value "820")
      (footprint "eagle-import:R0402")
      (libsource (lib "eagle-import") (part "R-EU_R0402"))
    )
    (comp (ref "R41")
      (value "820")
      (footprint "eagle-import:R0402")
      (libsource (lib "eagle-import") (part "R-EU_R0402"))
    )
    (comp (ref "R42")
      (value "820")
      (footprint "eagle-import:R0402")
      (libsource (lib "eagle-import") (part "R-EU_R0402"))
    )
    (comp (ref "R43")
      (value "820")
      (footprint "eagle-import:R0402")
      (libsource (lib "eagle-import") (part "R-EU_R0402"))
    )
    (comp (ref "R44")
      (value "820")
      (footprint "eagle-import:R0402")
      (libsource (lib "eagle-import") (part "R-EU_R0402"))
    )
    (comp (ref "R45")
      (value "820")
      (footprint "eagle-import:R0402")
      (libsource (lib "eagle-import") (part "R-EU_R0402"))
    )
    (comp (ref "R46")
      (value "820")
      (footprint "eagle-import:R0402")
      (libsource (lib "eagle-import") (part "R-EU_R0402"))
    )
    (comp (ref "R47")
      (value "820")
      (footprint "eagle-import:R0402")
      (libsource (lib "eagle-import") (part "R-EU_R0402"))
    )
    (comp (ref "R48")
      (value "820")
      (footprint "eagle-import:R0402")
      (libsource (lib "eagle-import") (part "R-EU_R0402"))
    )
    (comp (ref "R49")
      (value "820")
      (footprint "eagle-import:R0402")
      (libsource (lib "eagle-import") (part "R-EU_R0402"))
    )
    (comp (ref "R50")
      (value "820")
      (footprint "eagle-import:R0402")
      (libsource (lib "eagle-import") (part "R-EU_R0402"))
    )
    (comp (ref "R51")
      (value "820")
      (footprint "eagle-import:R0402")
      (libsource (lib "eagle-import") (part "R-EU_R0402"))
    )
    (comp (ref "R52")
      (value "820")
      (footprint "eagle-import:R0402")
      (libsource (lib "eagle-import") (part "R-EU_R0402"))
    )
    (comp (ref "R53")
      (value "820")
      (footprint "eagle-import:R0402")
      (libsource (lib "eagle-import") (part "R-EU_R0402"))
    )
    (comp (ref "R54")
      (value "820")
      (footprint "eagle-import:R0402")
      (libsource (lib "eagle-import") (part "R-EU_R0402"))
    )
    (comp (ref "R55")
      (value "820")
      (footprint "eagle-import:R0402")
      (libsource (lib "eagle-import") (part "R-EU_R0402"))
    )
    (comp (ref "R56")
      (value "820")
      (footprint "eagle-import:R0402")
      (libsource (lib "eagle-import") (part "R-EU_R0402"))
    )
    (comp (ref "R57")
      (value "820")
      (footprint "eagle-import:R0402")
      (libsource (lib "eagle-import") (part "R-EU_R0402"))
    )
    (comp (ref "R58")
      (value "820")
      (footprint "eagle-import:R0402")
      (libsource (lib "eagle-import") (part "R-EU_R0402"))
    )
    (comp (ref "R59")
      (value "820")
      (footprint "eagle-import:R0402")
      (libsource (lib "eagle-import") (part "R-EU_R0402"))
    )
    (comp (ref "R60")
      (value "820")
      (footprint "eagle-import:R0402")
      (libsource (lib "eagle-import") (part "R-EU_R0402"))
    )
    (comp (ref "R61")
      (value "820")
      (footprint "eagle-import:R0402")
      (libsource (lib "eagle-import") (part "R-EU_R0402"))
    )
    (comp (ref "R62")
      (value "820")
      (footprint "eagle-import:R0402")
      (libsource (lib "eagle-import") (part "R-EU_R0402"))
    )
    (comp (ref "R63")
      (value "820")
      (footprint "eagle-import:R0402")
      (libsource (lib "eagle-import") (part "R-EU_R0402"))
    )
    (comp (ref "R64")
      (value "820")
      (footprint "eagle-import:R0402")
      (libsource (lib "eagle-import") (part "R-EU_R0402"))
    )
    (comp (ref "R65")
      (value "820")
      (footprint "eagle-import:R0402")
      (libsource (lib "eagle-import") (part "R-EU_R0402"))
    )
    (comp (ref "R66")
      (value "820")
      (footprint "eagle-import:R0402")
      (libsource (lib "eagle-import") (part "R-EU_R0402"))
    )
    (comp (ref "R67")
      (value "820")
      (footprint "eagle-import:R0402")
      (libsource (lib "eagle-import") (part "R-EU_R0402"))
    )
    (comp (ref "R68")
      (value "820")
      (footprint "eagle-import:R0402")
      (libsource (lib "eagle-import") (part "R-EU_R0402"))
    )
    (comp (ref "R69")
      (value "820")
      (footprint "eagle-import:R0402")
      (libsource (lib "eagle-import") (part "R-EU_R0402"))
    )
    (comp (ref "R70")
      (value "820")
      (footprint "eagle-import:R0402")
      (libsource (lib "eagle-import") (part "R-EU_R0402"))
    )
    (comp (ref "R71")
      (value "820")
      (footprint "eagle-import:R0402")
      (libsource (lib "eagle-import") (part "R-EU_R0402"))
    )
    (comp (ref "R72")
      (value "820")
      (footprint "eagle-import:R0402")
      (libsource (lib "eagle-import") (part "R-EU_R0402"))
    )
    (comp (ref "R73")
      (value "820")
      (footprint "eagle-import:R0402")
      (libsource (lib "eagle-import") (part "R-EU_R0402"))
    )
    (comp (ref "R74")
      (value "820")
      (footprint "eagle-import:R0402")
      (libsource (lib "eagle-import") (part "R-EU_R0402"))
    )
    (comp (ref "R75")
      (value "820")
      (footprint "eagle-import:R0402")
      (libsource (lib "eagle-import") (part "R-EU_R0402"))
    )
    (comp (ref "R76")
      (value "820")
      (footprint "eagle-import:R0402")
      (libsource (lib "eagle-import") (part "R-EU_R0402"))
    )
    (comp (ref "R77")
      (value "820")
      (footprint "eagle-import:R0402")
      (libsource (lib "eagle-import") (part "R-EU_R0402"))
    )
    (comp (ref "R78")
      (value "820")
      (footprint "eagle-import:R0402")
      (libsource (lib "eagle-import") (part "R-EU_R0402"))
    )
    (comp (ref "R79")
      (value "820")
      (footprint "eagle-import:R0402")
      (libsource (lib "eagle-import") (part "R-EU_R0402"))
    )
    (comp (ref "R80")
      (value "820")
      (footprint "eagle-import:R0402")
      (libsource (lib "eagle-import") (part "R-EU_R0402"))
    )
    (comp (ref "R81")
      (value "820")
      (footprint "eagle-import:R0402")
      (libsource (lib "eagle-import") (part "R-EU_R0402"))
    )
    (comp (ref "R82")
      (value "820")
      (footprint "eagle-import:R0402")
      (libsource (lib "eagle-import") (part "R-EU_R0402"))
    )
    (comp (ref "R83")
      (value "820")
      (footprint "eagle-import:R0402")
      (libsource (lib "eagle-import") (part "R-EU_R0402"))
    )
    (comp (ref "R84")
      (value "820")
      (footprint "eagle-import:R0402")
      (libsource (lib "eagle-import") (part "R-EU_R0402"))
    )
    (comp (ref "R85")
      (value "820")
      (footprint "eagle-import:R0402")
      (libsource (lib "eagle-import") (part "R-EU_R0402"))
    )
    (comp (ref "R86")
      (value "820")
      (footprint "eagle-import:R0402")
      (libsource (lib "eagle-import") (part "R-EU_R0402"))
    )
    (comp (ref "R87")
      (value "820")
      (footprint "eagle-import:R0402")
      (libsource (lib "eagle-import") (part "R-EU_R0402"))
    )
    (comp (ref "R88")
      (value "820")
      (footprint "eagle-import:R0402")
      (libsource (lib "eagle-import") (part "R-EU_R0402"))
    )
    (comp (ref "R89")
      (value "820")
      (footprint "eagle-import:R0402")
      (libsource (lib "eagle-import") (part "R-EU_R0402"))
    )
    (comp (ref "R90")
      (value "820")
      (footprint "eagle-import:R0402")
      (libsource (lib "eagle-import") (part "R-EU_R0402"))
    )
    (comp (ref "R91")
      (value "820")
      (footprint "eagle-import:R0402")
      (libsource (lib "eagle-import") (part "R-EU_R0402"))
    )
    (comp (ref "R92")
      (value "820")
      (footprint "eagle-import:R0402")
      (libsource (lib "eagle-import") (part "R-EU_R0402"))
    )
    (comp (ref "R93")
      (value "820")
      (footprint "eagle-import:R0402")
      (libsource (lib "eagle-import") (part "R-EU_R0402"))
    )
    (comp (ref "R94")
      (value "820")
      (footprint "eagle-import:R0402")
      (libsource (lib "eagle-import") (part "R-EU_R0402"))
    )
    (comp (ref "R95")
      (value "820")
      (footprint "eagle-import:R0402")
      (libsource (lib "eagle-import") (part "R-EU_R0402"))
    )
    (comp (ref "R96")
      (value "820")
      (footprint "eagle-import:R0402")
      (libsource (lib "eagle-import") (part "R-EU_R0402"))
    )
    (comp (ref "R97")
      (value "820")
      (footprint "eagle-import:R0402")
      (libsource (lib "eagle-import") (part "R-EU_R0402"))
    )
    (comp (ref "R98")
      (value "820")
      (footprint "eagle-import:R0402")
      (libsource (lib "eagle-import") (part "R-EU_R0402"))
    )
    (comp (ref "R99")
      (value "820")
      (footprint "eagle-import:R0402")
      (libsource (lib "eagle-import") (part "R-EU_R0402"))
    )
    (comp (ref "R100")
      (value "820")
      (footprint "eagle-import:R0402")
      (libsource (lib "eagle-import") (part "R-EU_R0402"))
    )
    (comp (ref "R101")
      (value "820")
      (footprint "eagle-import:R0402")
      (libsource (lib "eagle-import") (part "R-EU_R0402"))
    )
    (comp (ref "R102")
      (value "820")
      (footprint "eagle-import:R0402")
      (libsource (lib "eagle-import") (part "R-EU_R0402"))
    )
    (comp (ref "R103")
      (value "820")
      (footprint "eagle-import:R0402")
      (libsource (lib "eagle-import") (part "R-EU_R0402"))
    )
    (comp (ref "R104")
      (value "820")
      (footprint "eagle-import:R0402")
      (libsource (lib "eagle-import") (part "R-EU_R0402"))
    )
    (comp (ref "R105")
      (value "820")
      (footprint "eagle-import:R0402")
      (libsource (lib "eagle-import") (part "R-EU_R0402"))
    )
    (comp (ref "R106")
      (value "820")
      (footprint "eagle-import:R0402")
      (libsource (lib "eagle-import") (part "R-EU_R0402"))
    )
    (comp (ref "R107")
      (value "820")
      (footprint "eagle-import:R0402")
      (libsource (lib "eagle-import") (part "R-EU_R0402"))
    )
    (comp (ref "R108")
      (value "820")
      (footprint "eagle-import:R0402")
      (libsource (lib "eagle-import") (part "R-EU_R0402"))
    )
    (comp (ref "R109")
      (value "820")
      (footprint "eagle-import:R0402")
      (libsource (lib "eagle-import") (part "R-EU_R0402"))
    )
    (comp (ref "R110")
      (value "820")
      (footprint "eagle-import:R0402")
      (libsource (lib "eagle-import") (part "R-EU_R0402"))
    )
    (comp (ref "R111")
      (value "820")
      (footprint "eagle-import:R0402")
      (libsource (lib "eagle-import") (part "R-EU_R0402"))
    )
    (comp (ref "R112")
      (value "820")
      (footprint "eagle-import:R0402")
      (libsource (lib "eagle-import") (part "R-EU_R0402"))
    )
    (comp (ref "R113")
      (value "820")
      (footprint "eagle-import:R0402")
      (libsource (lib "eagle-import") (part "R-EU_R0402"))
    )
    (comp (ref "R114")
      (value "820")
      (footprint "eagle-import:R0402")
      (libsource (lib "eagle-import") (part "R-EU_R0402"))
    )
    (comp (ref "R115")
      (value "820")
      (footprint "eagle-import:R0402")
      (libsource (lib "eagle-import") (part "R-EU_R0402"))
    )
    (comp (ref "R116")
      (value "820")
      (footprint "eagle-import:R0402")
      (libsource (lib "eagle-import") (part "R-EU_R0402"))
    )
  )
  (nets
    (net (code "1") (name "CH_1_IN") (class "Default")
      (node (ref "J1_1-32_IN") (pin "1") (pinfunction "1_1") (pintype "bidirectional"))
      (node (ref "R1") (pin "1") (pinfunction "1_1") (pintype "passive"))
    )
    (net (code "2") (name "CH_1_OUT") (class "Default")
      (node (ref "C2") (pin "1") (pinfunction "1_1") (pintype "passive"))
      (node (ref "J4_1-32_OUT") (pin "1") (pinfunction "1_1") (pintype "bidirectional"))
      (node (ref "R2") (pin "2") (pinfunction "2_2") (pintype "passive"))
    )
    (net (code "3") (name "CH_2_IN") (class "Default")
      (node (ref "J1_1-32_IN") (pin "4") (pinfunction "4_4") (pintype "bidirectional"))
      (node (ref "R3") (pin "1") (pinfunction "1_1") (pintype "passive"))
    )
    (net (code "4") (name "CH_2_OUT") (class "Default")
      (node (ref "C4") (pin "1") (pinfunction "1_1") (pintype "passive"))
      (node (ref "J4_1-32_OUT") (pin "4") (pinfunction "4_4") (pintype "bidirectional"))
      (node (ref "R4") (pin "2") (pinfunction "2_2") (pintype "passive"))
    )
    (net (code "5") (name "CH_3_IN") (class "Default")
      (node (ref "J1_1-32_IN") (pin "3") (pinfunction "3_3") (pintype "bidirectional"))
      (node (ref "R5") (pin "1") (pinfunction "1_1") (pintype "passive"))
    )
    (net (code "6") (name "CH_3_OUT") (class "Default")
      (node (ref "C6") (pin "1") (pinfunction "1_1") (pintype "passive"))
      (node (ref "J4_1-32_OUT") (pin "3") (pinfunction "3_3") (pintype "bidirectional"))
      (node (ref "R6") (pin "2") (pinfunction "2_2") (pintype "passive"))
    )
    (net (code "7") (name "CH_4_IN") (class "Default")
      (node (ref "J1_1-32_IN") (pin "6") (pinfunction "6_6") (pintype "bidirectional"))
      (node (ref "R7") (pin "1") (pinfunction "1_1") (pintype "passive"))
    )
    (net (code "8") (name "CH_4_OUT") (class "Default")
      (node (ref "C8") (pin "1") (pinfunction "1_1") (pintype "passive"))
      (node (ref "J4_1-32_OUT") (pin "6") (pinfunction "6_6") (pintype "bidirectional"))
      (node (ref "R8") (pin "2") (pinfunction "2_2") (pintype "passive"))
    )
    (net (code "9") (name "CH_5_IN") (class "Default")
      (node (ref "J1_1-32_IN") (pin "5") (pinfunction "5_5") (pintype "bidirectional"))
      (node (ref "R9") (pin "1") (pinfunction "1_1") (pintype "passive"))
    )
    (net (code "10") (name "CH_5_OUT") (class "Default")
      (node (ref "C10") (pin "1") (pinfunction "1_1") (pintype "passive"))
      (node (ref "J4_1-32_OUT") (pin "5") (pinfunction "5_5") (pintype "bidirectional"))
      (node (ref "R10") (pin "2") (pinfunction "2_2") (pintype "passive"))
    )
    (net (code "11") (name "CH_6_IN") (class "Default")
      (node (ref "J1_1-32_IN") (pin "8") (pinfunction "8_8") (pintype "bidirectional"))
      (node (ref "R11") (pin "1") (pinfunction "1_1") (pintype "passive"))
    )
    (net (code "12") (name "CH_6_OUT") (class "Default")
      (node (ref "C12") (pin "1") (pinfunction "1_1") (pintype "passive"))
      (node (ref "J4_1-32_OUT") (pin "8") (pinfunction "8_8") (pintype "bidirectional"))
      (node (ref "R12") (pin "2") (pinfunction "2_2") (pintype "passive"))
    )
    (net (code "13") (name "CH_7_IN") (class "Default")
      (node (ref "J1_1-32_IN") (pin "7") (pinfunction "7_7") (pintype "bidirectional"))
      (node (ref "R13") (pin "1") (pinfunction "1_1") (pintype "passive"))
    )
    (net (code "14") (name "CH_7_OUT") (class "Default")
      (node (ref "C14") (pin "1") (pinfunction "1_1") (pintype "passive"))
      (node (ref "J4_1-32_OUT") (pin "7") (pinfunction "7_7") (pintype "bidirectional"))
      (node (ref "R14") (pin "2") (pinfunction "2_2") (pintype "passive"))
    )
    (net (code "15") (name "CH_8_IN") (class "Default")
      (node (ref "J1_1-32_IN") (pin "10") (pinfunction "10_10") (pintype "bidirectional"))
      (node (ref "R15") (pin "1") (pinfunction "1_1") (pintype "passive"))
    )
    (net (code "16") (name "CH_8_OUT") (class "Default")
      (node (ref "C16") (pin "1") (pinfunction "1_1") (pintype "passive"))
      (node (ref "J4_1-32_OUT") (pin "10") (pinfunction "10_10") (pintype "bidirectional"))
      (node (ref "R16") (pin "2") (pinfunction "2_2") (pintype "passive"))
    )
    (net (code "17") (name "CH_9_IN") (class "Default")
      (node (ref "J1_1-32_IN") (pin "12") (pinfunction "12_12") (pintype "bidirectional"))
      (node (ref "R17") (pin "1") (pinfunction "1_1") (pintype "passive"))
    )
    (net (code "18") (name "CH_9_OUT") (class "Default")
      (node (ref "C18") (pin "1") (pinfunction "1_1") (pintype "passive"))
      (node (ref "J4_1-32_OUT") (pin "12") (pinfunction "12_12") (pintype "bidirectional"))
      (node (ref "R18") (pin "2") (pinfunction "2_2") (pintype "passive"))
    )
    (net (code "19") (name "CH_10_IN") (class "Default")
      (node (ref "J1_1-32_IN") (pin "11") (pinfunction "11_11") (pintype "bidirectional"))
      (node (ref "R19") (pin "1") (pinfunction "1_1") (pintype "passive"))
    )
    (net (code "20") (name "CH_10_OUT") (class "Default")
      (node (ref "C20") (pin "1") (pinfunction "1_1") (pintype "passive"))
      (node (ref "J4_1-32_OUT") (pin "11") (pinfunction "11_11") (pintype "bidirectional"))
      (node (ref "R20") (pin "2") (pinfunction "2_2") (pintype "passive"))
    )
    (net (code "21") (name "CH_11_IN") (class "Default")
      (node (ref "J1_1-32_IN") (pin "14") (pinfunction "14_14") (pintype "bidirectional"))
      (node (ref "R21") (pin "1") (pinfunction "1_1") (pintype "passive"))
    )
    (net (code "22") (name "CH_11_OUT") (class "Default")
      (node (ref "C22") (pin "1") (pinfunction "1_1") (pintype "passive"))
      (node (ref "J4_1-32_OUT") (pin "14") (pinfunction "14_14") (pintype "bidirectional"))
      (node (ref "R22") (pin "2") (pinfunction "2_2") (pintype "passive"))
    )
    (net (code "23") (name "CH_12_IN") (class "Default")
      (node (ref "J1_1-32_IN") (pin "13") (pinfunction "13_13") (pintype "bidirectional"))
      (node (ref "R23") (pin "1") (pinfunction "1_1") (pintype "passive"))
    )
    (net (code "24") (name "CH_12_OUT") (class "Default")
      (node (ref "C24") (pin "1") (pinfunction "1_1") (pintype "passive"))
      (node (ref "J4_1-32_OUT") (pin "13") (pinfunction "13_13") (pintype "bidirectional"))
      (node (ref "R24") (pin "2") (pinfunction "2_2") (pintype "passive"))
    )
    (net (code "25") (name "CH_13_IN") (class "Default")
      (node (ref "J1_1-32_IN") (pin "16") (pinfunction "16_16") (pintype "bidirectional"))
      (node (ref "R25") (pin "1") (pinfunction "1_1") (pintype "passive"))
    )
    (net (code "26") (name "CH_13_OUT") (class "Default")
      (node (ref "C26") (pin "1") (pinfunction "1_1") (pintype "passive"))
      (node (ref "J4_1-32_OUT") (pin "16") (pinfunction "16_16") (pintype "bidirectional"))
      (node (ref "R26") (pin "2") (pinfunction "2_2") (pintype "passive"))
    )
    (net (code "27") (name "CH_14_IN") (class "Default")
      (node (ref "J1_1-32_IN") (pin "15") (pinfunction "15_15") (pintype "bidirectional"))
      (node (ref "R27") (pin "1") (pinfunction "1_1") (pintype "passive"))
    )
    (net (code "28") (name "CH_14_OUT") (class "Default")
      (node (ref "C28") (pin "1") (pinfunction "1_1") (pintype "passive"))
      (node (ref "J4_1-32_OUT") (pin "15") (pinfunction "15_15") (pintype "bidirectional"))
      (node (ref "R28") (pin "2") (pinfunction "2_2") (pintype "passive"))
    )
    (net (code "29") (name "CH_15_IN") (class "Default")
      (node (ref "J1_1-32_IN") (pin "18") (pinfunction "18_18") (pintype "bidirectional"))
      (node (ref "R29") (pin "1") (pinfunction "1_1") (pintype "passive"))
    )
    (net (code "30") (name "CH_15_OUT") (class "Default")
      (node (ref "C30") (pin "1") (pinfunction "1_1") (pintype "passive"))
      (node (ref "J4_1-32_OUT") (pin "18") (pinfunction "18_18") (pintype "bidirectional"))
      (node (ref "R30") (pin "2") (pinfunction "2_2") (pintype "passive"))
    )
    (net (code "31") (name "CH_16_IN") (class "Default")
      (node (ref "J1_1-32_IN") (pin "17") (pinfunction "17_17") (pintype "bidirectional"))
      (node (ref "R31") (pin "1") (pinfunction "1_1") (pintype "passive"))
    )
    (net (code "32") (name "CH_16_OUT") (class "Default")
      (node (ref "C32") (pin "1") (pinfunction "1_1") (pintype "passive"))
      (node (ref "J4_1-32_OUT") (pin "17") (pinfunction "17_17") (pintype "bidirectional"))
      (node (ref "R32") (pin "2") (pinfunction "2_2") (pintype "passive"))
    )
    (net (code "33") (name "CH_17_IN") (class "Default")
      (node (ref "J1_1-32_IN") (pin "19") (pinfunction "19_19") (pintype "bidirectional"))
      (node (ref "R33") (pin "1") (pinfunction "1_1") (pintype "passive"))
    )
    (net (code "34") (name "CH_17_OUT") (class "Default")
      (node (ref "C34") (pin "1") (pinfunction "1_1") (pintype "passive"))
      (node (ref "J4_1-32_OUT") (pin "19") (pinfunction "19_19") (pintype "bidirectional"))
      (node (ref "R34") (pin "2") (pinfunction "2_2") (pintype "passive"))
    )
    (net (code "35") (name "CH_18_IN") (class "Default")
      (node (ref "J1_1-32_IN") (pin "22") (pinfunction "22_22") (pintype "bidirectional"))
      (node (ref "R35") (pin "1") (pinfunction "1_1") (pintype "passive"))
    )
    (net (code "36") (name "CH_18_OUT") (class "Default")
      (node (ref "C36") (pin "1") (pinfunction "1_1") (pintype "passive"))
      (node (ref "J4_1-32_OUT") (pin "22") (pinfunction "22_22") (pintype "bidirectional"))
      (node (ref "R36") (pin "2") (pinfunction "2_2") (pintype "passive"))
    )
    (net (code "37") (name "CH_19_IN") (class "Default")
      (node (ref "J1_1-32_IN") (pin "21") (pinfunction "21_21") (pintype "bidirectional"))
      (node (ref "R37") (pin "1") (pinfunction "1_1") (pintype "passive"))
    )
    (net (code "38") (name "CH_19_OUT") (class "Default")
      (node (ref "C38") (pin "1") (pinfunction "1_1") (pintype "passive"))
      (node (ref "J4_1-32_OUT") (pin "21") (pinfunction "21_21") (pintype "bidirectional"))
      (node (ref "R38") (pin "2") (pinfunction "2_2") (pintype "passive"))
    )
    (net (code "39") (name "CH_20_IN") (class "Default")
      (node (ref "J1_1-32_IN") (pin "24") (pinfunction "24_24") (pintype "bidirectional"))
      (node (ref "R39") (pin "1") (pinfunction "1_1") (pintype "passive"))
    )
    (net (code "40") (name "CH_20_OUT") (class "Default")
      (node (ref "C40") (pin "1") (pinfunction "1_1") (pintype "passive"))
      (node (ref "J4_1-32_OUT") (pin "24") (pinfunction "24_24") (pintype "bidirectional"))
      (node (ref "R40") (pin "2") (pinfunction "2_2") (pintype "passive"))
    )
    (net (code "41") (name "CH_21_IN") (class "Default")
      (node (ref "J1_1-32_IN") (pin "23") (pinfunction "23_23") (pintype "bidirectional"))
      (node (ref "R41") (pin "1") (pinfunction "1_1") (pintype "passive"))
    )
    (net (code "42") (name "CH_21_OUT") (class "Default")
      (node (ref "C42") (pin "1") (pinfunction "1_1") (pintype "passive"))
      (node (ref "J4_1-32_OUT") (pin "23") (pinfunction "23_23") (pintype "bidirectional"))
      (node (ref "R42") (pin "2") (pinfunction "2_2") (pintype "passive"))
    )
    (net (code "43") (name "CH_22_IN") (class "Default")
      (node (ref "J1_1-32_IN") (pin "26") (pinfunction "26_26") (pintype "bidirectional"))
      (node (ref "R43") (pin "1") (pinfunction "1_1") (pintype "passive"))
    )
    (net (code "44") (name "CH_22_OUT") (class "Default")
      (node (ref "C44") (pin "1") (pinfunction "1_1") (pintype "passive"))
      (node (ref "J4_1-32_OUT") (pin "26") (pinfunction "26_26") (pintype "bidirectional"))
      (node (ref "R44") (pin "2") (pinfunction "2_2") (pintype "passive"))
    )
    (net (code "45") (name "CH_23_IN") (class "Default")
      (node (ref "J1_1-32_IN") (pin "25") (pinfunction "25_25") (pintype "bidirectional"))
      (node (ref "R45") (pin "1") (pinfunction "1_1") (pintype "passive"))
    )
    (net (code "46") (name "CH_23_OUT") (class "Default")
      (node (ref "C46") (pin "1") (pinfunction "1_1") (pintype "passive"))
      (node (ref "J4_1-32_OUT") (pin "25") (pinfunction "25_25") (pintype "bidirectional"))
      (node (ref "R46") (pin "2") (pinfunction "2_2") (pintype "passive"))
    )
    (net (code "47") (name "CH_24_IN") (class "Default")
      (node (ref "J1_1-32_IN") (pin "28") (pinfunction "28_28") (pintype "bidirectional"))
      (node (ref "R47") (pin "1") (pinfunction "1_1") (pintype "passive"))
    )
    (net (code "48") (name "CH_24_OUT") (class "Default")
      (node (ref "C48") (pin "1") (pinfunction "1_1") (pintype "passive"))
      (node (ref "J4_1-32_OUT") (pin "28") (pinfunction "28_28") (pintype "bidirectional"))
      (node (ref "R48") (pin "2") (pinfunction "2_2") (pintype "passive"))
    )
    (net (code "49") (name "CH_25_IN") (class "Default")
      (node (ref "J1_1-32_IN") (pin "30") (pinfunction "30_30") (pintype "bidirectional"))
      (node (ref "R117") (pin "1") (pinfunction "1_1") (pintype "passive"))
    )
    (net (code "50") (name "CH_25_OUT") (class "Default")
      (node (ref "C118") (pin "1") (pinfunction "1_1") (pintype "passive"))
      (node (ref "J4_1-32_OUT") (pin "30") (pinfunction "30_30") (pintype "bidirectional"))
      (node (ref "R118") (pin "2") (pinfunction "2_2") (pintype "passive"))
    )
    (net (code "51") (name "CH_25_REF_IN") (class "Default")
      (node (ref "C117") (pin "2") (pinfunction "2_2") (pintype "passive"))
      (node (ref "C118") (pin "2") (pinfunction "2_2") (pintype "passive"))
      (node (ref "J3_REF_IN") (pin "1") (pinfunction "1_1") (pintype "bidirectional"))
      (node (ref "J6_REF_OUT") (pin "1") (pinfunction "1_1") (pintype "bidirectional"))
    )
    (net (code "52") (name "CH_26_IN") (class "Default")
      (node (ref "J1_1-32_IN") (pin "29") (pinfunction "29_29") (pintype "bidirectional"))
      (node (ref "R119") (pin "1") (pinfunction "1_1") (pintype "passive"))
    )
    (net (code "53") (name "CH_26_OUT") (class "Default")
      (node (ref "C120") (pin "1") (pinfunction "1_1") (pintype "passive"))
      (node (ref "J4_1-32_OUT") (pin "29") (pinfunction "29_29") (pintype "bidirectional"))
      (node (ref "R120") (pin "2") (pinfunction "2_2") (pintype "passive"))
    )
    (net (code "54") (name "CH_26_REF_IN") (class "Default")
      (node (ref "C119") (pin "2") (pinfunction "2_2") (pintype "passive"))
      (node (ref "C120") (pin "2") (pinfunction "2_2") (pintype "passive"))
      (node (ref "J3_REF_IN") (pin "4") (pinfunction "4_4") (pintype "bidirectional"))
      (node (ref "J6_REF_OUT") (pin "4") (pinfunction "4_4") (pintype "bidirectional"))
    )
    (net (code "55") (name "CH_27_IN") (class "Default")
      (node (ref "J1_1-32_IN") (pin "32") (pinfunction "32_32") (pintype "bidirectional"))
      (node (ref "R121") (pin "1") (pinfunction "1_1") (pintype "passive"))
    )
    (net (code "56") (name "CH_27_OUT") (class "Default")
      (node (ref "C122") (pin "1") (pinfunction "1_1") (pintype "passive"))
      (node (ref "J4_1-32_OUT") (pin "32") (pinfunction "32_32") (pintype "bidirectional"))
      (node (ref "R122") (pin "2") (pinfunction "2_2") (pintype "passive"))
    )
    (net (code "57") (name "CH_27_REF_IN") (class "Default")
      (node (ref "C121") (pin "2") (pinfunction "2_2") (pintype "passive"))
      (node (ref "C122") (pin "2") (pinfunction "2_2") (pintype "passive"))
      (node (ref "J3_REF_IN") (pin "3") (pinfunction "3_3") (pintype "bidirectional"))
      (node (ref "J6_REF_OUT") (pin "3") (pinfunction "3_3") (pintype "bidirectional"))
    )
    (net (code "58") (name "CH_28_IN") (class "Default")
      (node (ref "J1_1-32_IN") (pin "31") (pinfunction "31_31") (pintype "bidirectional"))
      (node (ref "R123") (pin "1") (pinfunction "1_1") (pintype "passive"))
    )
    (net (code "59") (name "CH_28_OUT") (class "Default")
      (node (ref "C124") (pin "1") (pinfunction "1_1") (pintype "passive"))
      (node (ref "J4_1-32_OUT") (pin "31") (pinfunction "31_31") (pintype "bidirectional"))
      (node (ref "R124") (pin "2") (pinfunction "2_2") (pintype "passive"))
    )
    (net (code "60") (name "CH_28_REF_IN") (class "Default")
      (node (ref "C123") (pin "2") (pinfunction "2_2") (pintype "passive"))
      (node (ref "C124") (pin "2") (pinfunction "2_2") (pintype "passive"))
      (node (ref "J3_REF_IN") (pin "6") (pinfunction "6_6") (pintype "bidirectional"))
      (node (ref "J6_REF_OUT") (pin "6") (pinfunction "6_6") (pintype "bidirectional"))
    )
    (net (code "61") (name "CH_29_IN") (class "Default")
      (node (ref "J1_1-32_IN") (pin "34") (pinfunction "34_34") (pintype "bidirectional"))
      (node (ref "R125") (pin "1") (pinfunction "1_1") (pintype "passive"))
    )
    (net (code "62") (name "CH_29_OUT") (class "Default")
      (node (ref "C126") (pin "1") (pinfunction "1_1") (pintype "passive"))
      (node (ref "J4_1-32_OUT") (pin "34") (pinfunction "34_34") (pintype "bidirectional"))
      (node (ref "R126") (pin "2") (pinfunction "2_2") (pintype "passive"))
    )
    (net (code "63") (name "CH_29_REF_IN") (class "Default")
      (node (ref "C125") (pin "2") (pinfunction "2_2") (pintype "passive"))
      (node (ref "C126") (pin "2") (pinfunction "2_2") (pintype "passive"))
      (node (ref "J3_REF_IN") (pin "5") (pinfunction "5_5") (pintype "bidirectional"))
      (node (ref "J6_REF_OUT") (pin "5") (pinfunction "5_5") (pintype "bidirectional"))
    )
    (net (code "64") (name "CH_30_IN") (class "Default")
      (node (ref "J1_1-32_IN") (pin "33") (pinfunction "33_33") (pintype "bidirectional"))
      (node (ref "R127") (pin "1") (pinfunction "1_1") (pintype "passive"))
    )
    (net (code "65") (name "CH_30_OUT") (class "Default")
      (node (ref "C128") (pin "1") (pinfunction "1_1") (pintype "passive"))
      (node (ref "J4_1-32_OUT") (pin "33") (pinfunction "33_33") (pintype "bidirectional"))
      (node (ref "R128") (pin "2") (pinfunction "2_2") (pintype "passive"))
    )
    (net (code "66") (name "CH_30_REF_IN") (class "Default")
      (node (ref "C127") (pin "2") (pinfunction "2_2") (pintype "passive"))
      (node (ref "C128") (pin "2") (pinfunction "2_2") (pintype "passive"))
      (node (ref "J3_REF_IN") (pin "8") (pinfunction "8_8") (pintype "bidirectional"))
      (node (ref "J6_REF_OUT") (pin "8") (pinfunction "8_8") (pintype "bidirectional"))
    )
    (net (code "67") (name "CH_31_IN") (class "Default")
      (node (ref "J1_1-32_IN") (pin "36") (pinfunction "36_36") (pintype "bidirectional"))
      (node (ref "R81") (pin "1") (pinfunction "1_1") (pintype "passive"))
    )
    (net (code "68") (name "CH_31_OUT") (class "Default")
      (node (ref "C82") (pin "1") (pinfunction "1_1") (pintype "passive"))
      (node (ref "J4_1-32_OUT") (pin "36") (pinfunction "36_36") (pintype "bidirectional"))
      (node (ref "R82") (pin "2") (pinfunction "2_2") (pintype "passive"))
    )
    (net (code "69") (name "CH_32_IN") (class "Default")
      (node (ref "J1_1-32_IN") (pin "35") (pinfunction "35_35") (pintype "bidirectional"))
      (node (ref "R83") (pin "1") (pinfunction "1_1") (pintype "passive"))
    )
    (net (code "70") (name "CH_32_OUT") (class "Default")
      (node (ref "C84") (pin "1") (pinfunction "1_1") (pintype "passive"))
      (node (ref "J4_1-32_OUT") (pin "35") (pinfunction "35_35") (pintype "bidirectional"))
      (node (ref "R84") (pin "2") (pinfunction "2_2") (pintype "passive"))
    )
    (net (code "71") (name "CH_33_IN") (class "Default")
      (node (ref "J2_33-64_IN") (pin "1") (pinfunction "1_1") (pintype "bidirectional"))
      (node (ref "R85") (pin "1") (pinfunction "1_1") (pintype "passive"))
    )
    (net (code "72") (name "CH_33_OUT") (class "Default")
      (node (ref "C86") (pin "1") (pinfunction "1_1") (pintype "passive"))
      (node (ref "J5_33-64_OUT") (pin "1") (pinfunction "1_1") (pintype "bidirectional"))
      (node (ref "R86") (pin "2") (pinfunction "2_2") (pintype "passive"))
    )
    (net (code "73") (name "CH_34_IN") (class "Default")
      (node (ref "J2_33-64_IN") (pin "4") (pinfunction "4_4") (pintype "bidirectional"))
      (node (ref "R87") (pin "1") (pinfunction "1_1") (pintype "passive"))
    )
    (net (code "74") (name "CH_34_OUT") (class "Default")
      (node (ref "C88") (pin "1") (pinfunction "1_1") (pintype "passive"))
      (node (ref "J5_33-64_OUT") (pin "4") (pinfunction "4_4") (pintype "bidirectional"))
      (node (ref "R88") (pin "2") (pinfunction "2_2") (pintype "passive"))
    )
    (net (code "75") (name "CH_35_IN") (class "Default")
      (node (ref "J2_33-64_IN") (pin "3") (pinfunction "3_3") (pintype "bidirectional"))
      (node (ref "R89") (pin "1") (pinfunction "1_1") (pintype "passive"))
    )
    (net (code "76") (name "CH_35_OUT") (class "Default")
      (node (ref "C90") (pin "1") (pinfunction "1_1") (pintype "passive"))
      (node (ref "J5_33-64_OUT") (pin "3") (pinfunction "3_3") (pintype "bidirectional"))
      (node (ref "R90") (pin "2") (pinfunction "2_2") (pintype "passive"))
    )
    (net (code "77") (name "CH_36_IN") (class "Default")
      (node (ref "J2_33-64_IN") (pin "6") (pinfunction "6_6") (pintype "bidirectional"))
      (node (ref "R49") (pin "1") (pinfunction "1_1") (pintype "passive"))
    )
    (net (code "78") (name "CH_36_OUT") (class "Default")
      (node (ref "C50") (pin "1") (pinfunction "1_1") (pintype "passive"))
      (node (ref "J5_33-64_OUT") (pin "6") (pinfunction "6_6") (pintype "bidirectional"))
      (node (ref "R50") (pin "2") (pinfunction "2_2") (pintype "passive"))
    )
    (net (code "79") (name "CH_37_IN") (class "Default")
      (node (ref "J2_33-64_IN") (pin "5") (pinfunction "5_5") (pintype "bidirectional"))
      (node (ref "R51") (pin "1") (pinfunction "1_1") (pintype "passive"))
    )
    (net (code "80") (name "CH_37_OUT") (class "Default")
      (node (ref "C52") (pin "1") (pinfunction "1_1") (pintype "passive"))
      (node (ref "J5_33-64_OUT") (pin "5") (pinfunction "5_5") (pintype "bidirectional"))
      (node (ref "R52") (pin "2") (pinfunction "2_2") (pintype "passive"))
    )
    (net (code "81") (name "CH_38_IN") (class "Default")
      (node (ref "J2_33-64_IN") (pin "8") (pinfunction "8_8") (pintype "bidirectional"))
      (node (ref "R53") (pin "1") (pinfunction "1_1") (pintype "passive"))
    )
    (net (code "82") (name "CH_38_OUT") (class "Default")
      (node (ref "C54") (pin "1") (pinfunction "1_1") (pintype "passive"))
      (node (ref "J5_33-64_OUT") (pin "8") (pinfunction "8_8") (pintype "bidirectional"))
      (node (ref "R54") (pin "2") (pinfunction "2_2") (pintype "passive"))
    )
    (net (code "83") (name "CH_39_IN") (class "Default")
      (node (ref "J2_33-64_IN") (pin "7") (pinfunction "7_7") (pintype "bidirectional"))
      (node (ref "R55") (pin "1") (pinfunction "1_1") (pintype "passive"))
    )
    (net (code "84") (name "CH_39_OUT") (class "Default")
      (node (ref "C56") (pin "1") (pinfunction "1_1") (pintype "passive"))
      (node (ref "J5_33-64_OUT") (pin "7") (pinfunction "7_7") (pintype "bidirectional"))
      (node (ref "R56") (pin "2") (pinfunction "2_2") (pintype "passive"))
    )
    (net (code "85") (name "CH_40_IN") (class "Default")
      (node (ref "J2_33-64_IN") (pin "10") (pinfunction "10_10") (pintype "bidirectional"))
      (node (ref "R57") (pin "1") (pinfunction "1_1") (pintype "passive"))
    )
    (net (code "86") (name "CH_40_OUT") (class "Default")
      (node (ref "C58") (pin "1") (pinfunction "1_1") (pintype "passive"))
      (node (ref "J5_33-64_OUT") (pin "10") (pinfunction "10_10") (pintype "bidirectional"))
      (node (ref "R58") (pin "2") (pinfunction "2_2") (pintype "passive"))
    )
    (net (code "87") (name "CH_41_IN") (class "Default")
      (node (ref "J2_33-64_IN") (pin "12") (pinfunction "12_12") (pintype "bidirectional"))
      (node (ref "R59") (pin "1") (pinfunction "1_1") (pintype "passive"))
    )
    (net (code "88") (name "CH_41_OUT") (class "Default")
      (node (ref "C60") (pin "1") (pinfunction "1_1") (pintype "passive"))
      (node (ref "J5_33-64_OUT") (pin "12") (pinfunction "12_12") (pintype "bidirectional"))
      (node (ref "R60") (pin "2") (pinfunction "2_2") (pintype "passive"))
    )
    (net (code "89") (name "CH_42_IN") (class "Default")
      (node (ref "J2_33-64_IN") (pin "11") (pinfunction "11_11") (pintype "bidirectional"))
      (node (ref "R61") (pin "1") (pinfunction "1_1") (pintype "passive"))
    )
    (net (code "90") (name "CH_42_OUT") (class "Default")
      (node (ref "C62") (pin "1") (pinfunction "1_1") (pintype "passive"))
      (node (ref "J5_33-64_OUT") (pin "11") (pinfunction "11_11") (pintype "bidirectional"))
      (node (ref "R62") (pin "2") (pinfunction "2_2") (pintype "passive"))
    )
    (net (code "91") (name "CH_43_IN") (class "Default")
      (node (ref "J2_33-64_IN") (pin "14") (pinfunction "14_14") (pintype "bidirectional"))
      (node (ref "R63") (pin "1") (pinfunction "1_1") (pintype "passive"))
    )
    (net (code "92") (name "CH_43_OUT") (class "Default")
      (node (ref "C64") (pin "1") (pinfunction "1_1") (pintype "passive"))
      (node (ref "J5_33-64_OUT") (pin "14") (pinfunction "14_14") (pintype "bidirectional"))
      (node (ref "R64") (pin "2") (pinfunction "2_2") (pintype "passive"))
    )
    (net (code "93") (name "CH_44_IN") (class "Default")
      (node (ref "J2_33-64_IN") (pin "13") (pinfunction "13_13") (pintype "bidirectional"))
      (node (ref "R65") (pin "1") (pinfunction "1_1") (pintype "passive"))
    )
    (net (code "94") (name "CH_44_OUT") (class "Default")
      (node (ref "C66") (pin "1") (pinfunction "1_1") (pintype "passive"))
      (node (ref "J5_33-64_OUT") (pin "13") (pinfunction "13_13") (pintype "bidirectional"))
      (node (ref "R66") (pin "2") (pinfunction "2_2") (pintype "passive"))
    )
    (net (code "95") (name "CH_45_IN") (class "Default")
      (node (ref "J2_33-64_IN") (pin "16") (pinfunction "16_16") (pintype "bidirectional"))
      (node (ref "R67") (pin "1") (pinfunction "1_1") (pintype "passive"))
    )
    (net (code "96") (name "CH_45_OUT") (class "Default")
      (node (ref "C68") (pin "1") (pinfunction "1_1") (pintype "passive"))
      (node (ref "J5_33-64_OUT") (pin "16") (pinfunction "16_16") (pintype "bidirectional"))
      (node (ref "R68") (pin "2") (pinfunction "2_2") (pintype "passive"))
    )
    (net (code "97") (name "CH_46_IN") (class "Default")
      (node (ref "J2_33-64_IN") (pin "15") (pinfunction "15_15") (pintype "bidirectional"))
      (node (ref "R69") (pin "1") (pinfunction "1_1") (pintype "passive"))
    )
    (net (code "98") (name "CH_46_OUT") (class "Default")
      (node (ref "C70") (pin "1") (pinfunction "1_1") (pintype "passive"))
      (node (ref "J5_33-64_OUT") (pin "15") (pinfunction "15_15") (pintype "bidirectional"))
      (node (ref "R70") (pin "2") (pinfunction "2_2") (pintype "passive"))
    )
    (net (code "99") (name "CH_47_IN") (class "Default")
      (node (ref "J2_33-64_IN") (pin "18") (pinfunction "18_18") (pintype "bidirectional"))
      (node (ref "R71") (pin "1") (pinfunction "1_1") (pintype "passive"))
    )
    (net (code "100") (name "CH_47_OUT") (class "Default")
      (node (ref "C72") (pin "1") (pinfunction "1_1") (pintype "passive"))
      (node (ref "J5_33-64_OUT") (pin "18") (pinfunction "18_18") (pintype "bidirectional"))
      (node (ref "R72") (pin "2") (pinfunction "2_2") (pintype "passive"))
    )
    (net (code "101") (name "CH_48_IN") (class "Default")
      (node (ref "J2_33-64_IN") (pin "17") (pinfunction "17_17") (pintype "bidirectional"))
      (node (ref "R73") (pin "1") (pinfunction "1_1") (pintype "passive"))
    )
    (net (code "102") (name "CH_48_OUT") (class "Default")
      (node (ref "C74") (pin "1") (pinfunction "1_1") (pintype "passive"))
      (node (ref "J5_33-64_OUT") (pin "17") (pinfunction "17_17") (pintype "bidirectional"))
      (node (ref "R74") (pin "2") (pinfunction "2_2") (pintype "passive"))
    )
    (net (code "103") (name "CH_49_IN") (class "Default")
      (node (ref "J2_33-64_IN") (pin "19") (pinfunction "19_19") (pintype "bidirectional"))
      (node (ref "R75") (pin "1") (pinfunction "1_1") (pintype "passive"))
    )
    (net (code "104") (name "CH_49_OUT") (class "Default")
      (node (ref "C76") (pin "1") (pinfunction "1_1") (pintype "passive"))
      (node (ref "J5_33-64_OUT") (pin "19") (pinfunction "19_19") (pintype "bidirectional"))
      (node (ref "R76") (pin "2") (pinfunction "2_2") (pintype "passive"))
    )
    (net (code "105") (name "CH_50_IN") (class "Default")
      (node (ref "J2_33-64_IN") (pin "22") (pinfunction "22_22") (pintype "bidirectional"))
      (node (ref "R77") (pin "1") (pinfunction "1_1") (pintype "passive"))
    )
    (net (code "106") (name "CH_50_OUT") (class "Default")
      (node (ref "C78") (pin "1") (pinfunction "1_1") (pintype "passive"))
      (node (ref "J5_33-64_OUT") (pin "22") (pinfunction "22_22") (pintype "bidirectional"))
      (node (ref "R78") (pin "2") (pinfunction "2_2") (pintype "passive"))
    )
    (net (code "107") (name "CH_51_IN") (class "Default")
      (node (ref "J2_33-64_IN") (pin "21") (pinfunction "21_21") (pintype "bidirectional"))
      (node (ref "R79") (pin "1") (pinfunction "1_1") (pintype "passive"))
    )
    (net (code "108") (name "CH_51_OUT") (class "Default")
      (node (ref "C80") (pin "1") (pinfunction "1_1") (pintype "passive"))
      (node (ref "J5_33-64_OUT") (pin "21") (pinfunction "21_21") (pintype "bidirectional"))
      (node (ref "R80") (pin "2") (pinfunction "2_2") (pintype "passive"))
    )
    (net (code "109") (name "CH_52_IN") (class "Default")
      (node (ref "J2_33-64_IN") (pin "24") (pinfunction "24_24") (pintype "bidirectional"))
      (node (ref "R91") (pin "1") (pinfunction "1_1") (pintype "passive"))
    )
    (net (code "110") (name "CH_52_OUT") (class "Default")
      (node (ref "C92") (pin "1") (pinfunction "1_1") (pintype "passive"))
      (node (ref "J5_33-64_OUT") (pin "24") (pinfunction "24_24") (pintype "bidirectional"))
      (node (ref "R92") (pin "2") (pinfunction "2_2") (pintype "passive"))
    )
    (net (code "111") (name "CH_53_IN") (class "Default")
      (node (ref "J2_33-64_IN") (pin "23") (pinfunction "23_23") (pintype "bidirectional"))
      (node (ref "R93") (pin "1") (pinfunction "1_1") (pintype "passive"))
    )
    (net (code "112") (name "CH_53_OUT") (class "Default")
      (node (ref "C94") (pin "1") (pinfunction "1_1") (pintype "passive"))
      (node (ref "J5_33-64_OUT") (pin "23") (pinfunction "23_23") (pintype "bidirectional"))
      (node (ref "R94") (pin "2") (pinfunction "2_2") (pintype "passive"))
    )
    (net (code "113") (name "CH_54_IN") (class "Default")
      (node (ref "J2_33-64_IN") (pin "26") (pinfunction "26_26") (pintype "bidirectional"))
      (node (ref "R95") (pin "1") (pinfunction "1_1") (pintype "passive"))
    )
    (net (code "114") (name "CH_54_OUT") (class "Default")
      (node (ref "C96") (pin "1") (pinfunction "1_1") (pintype "passive"))
      (node (ref "J5_33-64_OUT") (pin "26") (pinfunction "26_26") (pintype "bidirectional"))
      (node (ref "R96") (pin "2") (pinfunction "2_2") (pintype "passive"))
    )
    (net (code "115") (name "CH_55_IN") (class "Default")
      (node (ref "J2_33-64_IN") (pin "25") (pinfunction "25_25") (pintype "bidirectional"))
      (node (ref "R97") (pin "1") (pinfunction "1_1") (pintype "passive"))
    )
    (net (code "116") (name "CH_55_OUT") (class "Default")
      (node (ref "C98") (pin "1") (pinfunction "1_1") (pintype "passive"))
      (node (ref "J5_33-64_OUT") (pin "25") (pinfunction "25_25") (pintype "bidirectional"))
      (node (ref "R98") (pin "2") (pinfunction "2_2") (pintype "passive"))
    )
    (net (code "117") (name "CH_56_IN") (class "Default")
      (node (ref "J2_33-64_IN") (pin "28") (pinfunction "28_28") (pintype "bidirectional"))
      (node (ref "R99") (pin "1") (pinfunction "1_1") (pintype "passive"))
    )
    (net (code "118") (name "CH_56_OUT") (class "Default")
      (node (ref "C100") (pin "1") (pinfunction "1_1") (pintype "passive"))
      (node (ref "J5_33-64_OUT") (pin "28") (pinfunction "28_28") (pintype "bidirectional"))
      (node (ref "R100") (pin "2") (pinfunction "2_2") (pintype "passive"))
    )
    (net (code "119") (name "CH_57_IN") (class "Default")
      (node (ref "J2_33-64_IN") (pin "30") (pinfunction "30_30") (pintype "bidirectional"))
      (node (ref "R101") (pin "1") (pinfunction "1_1") (pintype "passive"))
    )
    (net (code "120") (name "CH_57_OUT") (class "Default")
      (node (ref "C102") (pin "1") (pinfunction "1_1") (pintype "passive"))
      (node (ref "J5_33-64_OUT") (pin "30") (pinfunction "30_30") (pintype "bidirectional"))
      (node (ref "R102") (pin "2") (pinfunction "2_2") (pintype "passive"))
    )
    (net (code "121") (name "CH_58_IN") (class "Default")
      (node (ref "J2_33-64_IN") (pin "29") (pinfunction "29_29") (pintype "bidirectional"))
      (node (ref "R103") (pin "1") (pinfunction "1_1") (pintype "passive"))
    )
    (net (code "122") (name "CH_58_OUT") (class "Default")
      (node (ref "C104") (pin "1") (pinfunction "1_1") (pintype "passive"))
      (node (ref "J5_33-64_OUT") (pin "29") (pinfunction "29_29") (pintype "bidirectional"))
      (node (ref "R104") (pin "2") (pinfunction "2_2") (pintype "passive"))
    )
    (net (code "123") (name "CH_59_IN") (class "Default")
      (node (ref "J2_33-64_IN") (pin "32") (pinfunction "32_32") (pintype "bidirectional"))
      (node (ref "R105") (pin "1") (pinfunction "1_1") (pintype "passive"))
    )
    (net (code "124") (name "CH_59_OUT") (class "Default")
      (node (ref "C106") (pin "1") (pinfunction "1_1") (pintype "passive"))
      (node (ref "J5_33-64_OUT") (pin "32") (pinfunction "32_32") (pintype "bidirectional"))
      (node (ref "R106") (pin "2") (pinfunction "2_2") (pintype "passive"))
    )
    (net (code "125") (name "CH_60_IN") (class "Default")
      (node (ref "J2_33-64_IN") (pin "31") (pinfunction "31_31") (pintype "bidirectional"))
      (node (ref "R107") (pin "1") (pinfunction "1_1") (pintype "passive"))
    )
    (net (code "126") (name "CH_60_OUT") (class "Default")
      (node (ref "C108") (pin "1") (pinfunction "1_1") (pintype "passive"))
      (node (ref "J5_33-64_OUT") (pin "31") (pinfunction "31_31") (pintype "bidirectional"))
      (node (ref "R108") (pin "2") (pinfunction "2_2") (pintype "passive"))
    )
    (net (code "127") (name "CH_61_IN") (class "Default")
      (node (ref "J2_33-64_IN") (pin "34") (pinfunction "34_34") (pintype "bidirectional"))
      (node (ref "R109") (pin "1") (pinfunction "1_1") (pintype "passive"))
    )
    (net (code "128") (name "CH_61_OUT") (class "Default")
      (node (ref "C110") (pin "1") (pinfunction "1_1") (pintype "passive"))
      (node (ref "J5_33-64_OUT") (pin "34") (pinfunction "34_34") (pintype "bidirectional"))
      (node (ref "R110") (pin "2") (pinfunction "2_2") (pintype "passive"))
    )
    (net (code "129") (name "CH_62_IN") (class "Default")
      (node (ref "J2_33-64_IN") (pin "33") (pinfunction "33_33") (pintype "bidirectional"))
      (node (ref "R111") (pin "1") (pinfunction "1_1") (pintype "passive"))
    )
    (net (code "130") (name "CH_62_OUT") (class "Default")
      (node (ref "C112") (pin "1") (pinfunction "1_1") (pintype "passive"))
      (node (ref "J5_33-64_OUT") (pin "33") (pinfunction "33_33") (pintype "bidirectional"))
      (node (ref "R112") (pin "2") (pinfunction "2_2") (pintype "passive"))
    )
    (net (code "131") (name "CH_63_IN") (class "Default")
      (node (ref "J2_33-64_IN") (pin "36") (pinfunction "36_36") (pintype "bidirectional"))
      (node (ref "R113") (pin "1") (pinfunction "1_1") (pintype "passive"))
    )
    (net (code "132") (name "CH_63_OUT") (class "Default")
      (node (ref "C114") (pin "1") (pinfunction "1_1") (pintype "passive"))
      (node (ref "J5_33-64_OUT") (pin "36") (pinfunction "36_36") (pintype "bidirectional"))
      (node (ref "R114") (pin "2") (pinfunction "2_2") (pintype "passive"))
    )
    (net (code "133") (name "CH_64_IN") (class "Default")
      (node (ref "J2_33-64_IN") (pin "35") (pinfunction "35_35") (pintype "bidirectional"))
      (node (ref "R115") (pin "1") (pinfunction "1_1") (pintype "passive"))
    )
    (net (code "134") (name "CH_64_OUT") (class "Default")
      (node (ref "C116") (pin "1") (pinfunction "1_1") (pintype "passive"))
      (node (ref "J5_33-64_OUT") (pin "35") (pinfunction "35_35") (pintype "bidirectional"))
      (node (ref "R116") (pin "2") (pinfunction "2_2") (pintype "passive"))
    )
    (net (code "135") (name "G1") (class "Default")
      (node (ref "J3_REF_IN") (pin "35") (pinfunction "35_35") (pintype "bidirectional"))
      (node (ref "J6_REF_OUT") (pin "35") (pinfunction "35_35") (pintype "bidirectional"))
    )
    (net (code "136") (name "G2") (class "Default")
      (node (ref "C1") (pin "2") (pinfunction "2_2") (pintype "passive"))
      (node (ref "C10") (pin "2") (pinfunction "2_2") (pintype "passive"))
      (node (ref "C100") (pin "2") (pinfunction "2_2") (pintype "passive"))
      (node (ref "C101") (pin "2") (pinfunction "2_2") (pintype "passive"))
      (node (ref "C102") (pin "2") (pinfunction "2_2") (pintype "passive"))
      (node (ref "C103") (pin "2") (pinfunction "2_2") (pintype "passive"))
      (node (ref "C104") (pin "2") (pinfunction "2_2") (pintype "passive"))
      (node (ref "C105") (pin "2") (pinfunction "2_2") (pintype "passive"))
      (node (ref "C106") (pin "2") (pinfunction "2_2") (pintype "passive"))
      (node (ref "C107") (pin "2") (pinfunction "2_2") (pintype "passive"))
      (node (ref "C108") (pin "2") (pinfunction "2_2") (pintype "passive"))
      (node (ref "C109") (pin "2") (pinfunction "2_2") (pintype "passive"))
      (node (ref "C11") (pin "2") (pinfunction "2_2") (pintype "passive"))
      (node (ref "C110") (pin "2") (pinfunction "2_2") (pintype "passive"))
      (node (ref "C111") (pin "2") (pinfunction "2_2") (pintype "passive"))
      (node (ref "C112") (pin "2") (pinfunction "2_2") (pintype "passive"))
      (node (ref "C113") (pin "2") (pinfunction "2_2") (pintype "passive"))
      (node (ref "C114") (pin "2") (pinfunction "2_2") (pintype "passive"))
      (node (ref "C115") (pin "2") (pinfunction "2_2") (pintype "passive"))
      (node (ref "C116") (pin "2") (pinfunction "2_2") (pintype "passive"))
      (node (ref "C12") (pin "2") (pinfunction "2_2") (pintype "passive"))
      (node (ref "C13") (pin "2") (pinfunction "2_2") (pintype "passive"))
      (node (ref "C14") (pin "2") (pinfunction "2_2") (pintype "passive"))
      (node (ref "C15") (pin "2") (pinfunction "2_2") (pintype "passive"))
      (node (ref "C16") (pin "2") (pinfunction "2_2") (pintype "passive"))
      (node (ref "C17") (pin "2") (pinfunction "2_2") (pintype "passive"))
      (node (ref "C18") (pin "2") (pinfunction "2_2") (pintype "passive"))
      (node (ref "C19") (pin "2") (pinfunction "2_2") (pintype "passive"))
      (node (ref "C2") (pin "2") (pinfunction "2_2") (pintype "passive"))
      (node (ref "C20") (pin "2") (pinfunction "2_2") (pintype "passive"))
      (node (ref "C21") (pin "2") (pinfunction "2_2") (pintype "passive"))
      (node (ref "C22") (pin "2") (pinfunction "2_2") (pintype "passive"))
      (node (ref "C23") (pin "2") (pinfunction "2_2") (pintype "passive"))
      (node (ref "C24") (pin "2") (pinfunction "2_2") (pintype "passive"))
      (node (ref "C25") (pin "2") (pinfunction "2_2") (pintype "passive"))
      (node (ref "C26") (pin "2") (pinfunction "2_2") (pintype "passive"))
      (node (ref "C27") (pin "2") (pinfunction "2_2") (pintype "passive"))
      (node (ref "C28") (pin "2") (pinfunction "2_2") (pintype "passive"))
      (node (ref "C29") (pin "2") (pinfunction "2_2") (pintype "passive"))
      (node (ref "C3") (pin "2") (pinfunction "2_2") (pintype "passive"))
      (node (ref "C30") (pin "2") (pinfunction "2_2") (pintype "passive"))
      (node (ref "C31") (pin "2") (pinfunction "2_2") (pintype "passive"))
      (node (ref "C32") (pin "2") (pinfunction "2_2") (pintype "passive"))
      (node (ref "C33") (pin "2") (pinfunction "2_2") (pintype "passive"))
      (node (ref "C34") (pin "2") (pinfunction "2_2") (pintype "passive"))
      (node (ref "C35") (pin "2") (pinfunction "2_2") (pintype "passive"))
      (node (ref "C36") (pin "2") (pinfunction "2_2") (pintype "passive"))
      (node (ref "C37") (pin "2") (pinfunction "2_2") (pintype "passive"))
      (node (ref "C38") (pin "2") (pinfunction "2_2") (pintype "passive"))
      (node (ref "C39") (pin "2") (pinfunction "2_2") (pintype "passive"))
      (node (ref "C4") (pin "2") (pinfunction "2_2") (pintype "passive"))
      (node (ref "C40") (pin "2") (pinfunction "2_2") (pintype "passive"))
      (node (ref "C41") (pin "2") (pinfunction "2_2") (pintype "passive"))
      (node (ref "C42") (pin "2") (pinfunction "2_2") (pintype "passive"))
      (node (ref "C43") (pin "2") (pinfunction "2_2") (pintype "passive"))
      (node (ref "C44") (pin "2") (pinfunction "2_2") (pintype "passive"))
      (node (ref "C45") (pin "2") (pinfunction "2_2") (pintype "passive"))
      (node (ref "C46") (pin "2") (pinfunction "2_2") (pintype "passive"))
      (node (ref "C47") (pin "2") (pinfunction "2_2") (pintype "passive"))
      (node (ref "C48") (pin "2") (pinfunction "2_2") (pintype "passive"))
      (node (ref "C49") (pin "2") (pinfunction "2_2") (pintype "passive"))
      (node (ref "C5") (pin "2") (pinfunction "2_2") (pintype "passive"))
      (node (ref "C50") (pin "2") (pinfunction "2_2") (pintype "passive"))
      (node (ref "C51") (pin "2") (pinfunction "2_2") (pintype "passive"))
      (node (ref "C52") (pin "2") (pinfunction "2_2") (pintype "passive"))
      (node (ref "C53") (pin "2") (pinfunction "2_2") (pintype "passive"))
      (node (ref "C54") (pin "2") (pinfunction "2_2") (pintype "passive"))
      (node (ref "C55") (pin "2") (pinfunction "2_2") (pintype "passive"))
      (node (ref "C56") (pin "2") (pinfunction "2_2") (pintype "passive"))
      (node (ref "C57") (pin "2") (pinfunction "2_2") (pintype "passive"))
      (node (ref "C58") (pin "2") (pinfunction "2_2") (pintype "passive"))
      (node (ref "C59") (pin "2") (pinfunction "2_2") (pintype "passive"))
      (node (ref "C6") (pin "2") (pinfunction "2_2") (pintype "passive"))
      (node (ref "C60") (pin "2") (pinfunction "2_2") (pintype "passive"))
      (node (ref "C61") (pin "2") (pinfunction "2_2") (pintype "passive"))
      (node (ref "C62") (pin "2") (pinfunction "2_2") (pintype "passive"))
      (node (ref "C63") (pin "2") (pinfunction "2_2") (pintype "passive"))
      (node (ref "C64") (pin "2") (pinfunction "2_2") (pintype "passive"))
      (node (ref "C65") (pin "2") (pinfunction "2_2") (pintype "passive"))
      (node (ref "C66") (pin "2") (pinfunction "2_2") (pintype "passive"))
      (node (ref "C67") (pin "2") (pinfunction "2_2") (pintype "passive"))
      (node (ref "C68") (pin "2") (pinfunction "2_2") (pintype "passive"))
      (node (ref "C69") (pin "2") (pinfunction "2_2") (pintype "passive"))
      (node (ref "C7") (pin "2") (pinfunction "2_2") (pintype "passive"))
      (node (ref "C70") (pin "2") (pinfunction "2_2") (pintype "passive"))
      (node (ref "C71") (pin "2") (pinfunction "2_2") (pintype "passive"))
      (node (ref "C72") (pin "2") (pinfunction "2_2") (pintype "passive"))
      (node (ref "C73") (pin "2") (pinfunction "2_2") (pintype "passive"))
      (node (ref "C74") (pin "2") (pinfunction "2_2") (pintype "passive"))
      (node (ref "C75") (pin "2") (pinfunction "2_2") (pintype "passive"))
      (node (ref "C76") (pin "2") (pinfunction "2_2") (pintype "passive"))
      (node (ref "C77") (pin "2") (pinfunction "2_2") (pintype "passive"))
      (node (ref "C78") (pin "2") (pinfunction "2_2") (pintype "passive"))
      (node (ref "C79") (pin "2") (pinfunction "2_2") (pintype "passive"))
      (node (ref "C8") (pin "2") (pinfunction "2_2") (pintype "passive"))
      (node (ref "C80") (pin "2") (pinfunction "2_2") (pintype "passive"))
      (node (ref "C81") (pin "2") (pinfunction "2_2") (pintype "passive"))
      (node (ref "C82") (pin "2") (pinfunction "2_2") (pintype "passive"))
      (node (ref "C83") (pin "2") (pinfunction "2_2") (pintype "passive"))
      (node (ref "C84") (pin "2") (pinfunction "2_2") (pintype "passive"))
      (node (ref "C85") (pin "2") (pinfunction "2_2") (pintype "passive"))
      (node (ref "C86") (pin "2") (pinfunction "2_2") (pintype "passive"))
      (node (ref "C87") (pin "2") (pinfunction "2_2") (pintype "passive"))
      (node (ref "C88") (pin "2") (pinfunction "2_2") (pintype "passive"))
      (node (ref "C89") (pin "2") (pinfunction "2_2") (pintype "passive"))
      (node (ref "C9") (pin "2") (pinfunction "2_2") (pintype "passive"))
      (node (ref "C90") (pin "2") (pinfunction "2_2") (pintype "passive"))
      (node (ref "C91") (pin "2") (pinfunction "2_2") (pintype "passive"))
      (node (ref "C92") (pin "2") (pinfunction "2_2") (pintype "passive"))
      (node (ref "C93") (pin "2") (pinfunction "2_2") (pintype "passive"))
      (node (ref "C94") (pin "2") (pinfunction "2_2") (pintype "passive"))
      (node (ref "C95") (pin "2") (pinfunction "2_2") (pintype "passive"))
      (node (ref "C96") (pin "2") (pinfunction "2_2") (pintype "passive"))
      (node (ref "C97") (pin "2") (pinfunction "2_2") (pintype "passive"))
      (node (ref "C98") (pin "2") (pinfunction "2_2") (pintype "passive"))
      (node (ref "C99") (pin "2") (pinfunction "2_2") (pintype "passive"))
      (node (ref "J3_REF_IN") (pin "36") (pinfunction "36_36") (pintype "bidirectional"))
      (node (ref "J6_REF_OUT") (pin "36") (pinfunction "36_36") (pintype "bidirectional"))
    )
    (net (code "137") (name "Net-(C1-Pad1)") (class "Default")
      (node (ref "C1") (pin "1") (pinfunction "1_1") (pintype "passive"))
      (node (ref "R1") (pin "2") (pinfunction "2_2") (pintype "passive"))
      (node (ref "R2") (pin "1") (pinfunction "1_1") (pintype "passive"))
    )
    (net (code "138") (name "Net-(C3-Pad1)") (class "Default")
      (node (ref "C3") (pin "1") (pinfunction "1_1") (pintype "passive"))
      (node (ref "R3") (pin "2") (pinfunction "2_2") (pintype "passive"))
      (node (ref "R4") (pin "1") (pinfunction "1_1") (pintype "passive"))
    )
    (net (code "139") (name "Net-(C5-Pad1)") (class "Default")
      (node (ref "C5") (pin "1") (pinfunction "1_1") (pintype "passive"))
      (node (ref "R5") (pin "2") (pinfunction "2_2") (pintype "passive"))
      (node (ref "R6") (pin "1") (pinfunction "1_1") (pintype "passive"))
    )
    (net (code "140") (name "Net-(C7-Pad1)") (class "Default")
      (node (ref "C7") (pin "1") (pinfunction "1_1") (pintype "passive"))
      (node (ref "R7") (pin "2") (pinfunction "2_2") (pintype "passive"))
      (node (ref "R8") (pin "1") (pinfunction "1_1") (pintype "passive"))
    )
    (net (code "141") (name "Net-(C9-Pad1)") (class "Default")
      (node (ref "C9") (pin "1") (pinfunction "1_1") (pintype "passive"))
      (node (ref "R10") (pin "1") (pinfunction "1_1") (pintype "passive"))
      (node (ref "R9") (pin "2") (pinfunction "2_2") (pintype "passive"))
    )
    (net (code "142") (name "Net-(C11-Pad1)") (class "Default")
      (node (ref "C11") (pin "1") (pinfunction "1_1") (pintype "passive"))
      (node (ref "R11") (pin "2") (pinfunction "2_2") (pintype "passive"))
      (node (ref "R12") (pin "1") (pinfunction "1_1") (pintype "passive"))
    )
    (net (code "143") (name "Net-(C13-Pad1)") (class "Default")
      (node (ref "C13") (pin "1") (pinfunction "1_1") (pintype "passive"))
      (node (ref "R13") (pin "2") (pinfunction "2_2") (pintype "passive"))
      (node (ref "R14") (pin "1") (pinfunction "1_1") (pintype "passive"))
    )
    (net (code "144") (name "Net-(C15-Pad1)") (class "Default")
      (node (ref "C15") (pin "1") (pinfunction "1_1") (pintype "passive"))
      (node (ref "R15") (pin "2") (pinfunction "2_2") (pintype "passive"))
      (node (ref "R16") (pin "1") (pinfunction "1_1") (pintype "passive"))
    )
    (net (code "145") (name "Net-(C17-Pad1)") (class "Default")
      (node (ref "C17") (pin "1") (pinfunction "1_1") (pintype "passive"))
      (node (ref "R17") (pin "2") (pinfunction "2_2") (pintype "passive"))
      (node (ref "R18") (pin "1") (pinfunction "1_1") (pintype "passive"))
    )
    (net (code "146") (name "Net-(C19-Pad1)") (class "Default")
      (node (ref "C19") (pin "1") (pinfunction "1_1") (pintype "passive"))
      (node (ref "R19") (pin "2") (pinfunction "2_2") (pintype "passive"))
      (node (ref "R20") (pin "1") (pinfunction "1_1") (pintype "passive"))
    )
    (net (code "147") (name "Net-(C21-Pad1)") (class "Default")
      (node (ref "C21") (pin "1") (pinfunction "1_1") (pintype "passive"))
      (node (ref "R21") (pin "2") (pinfunction "2_2") (pintype "passive"))
      (node (ref "R22") (pin "1") (pinfunction "1_1") (pintype "passive"))
    )
    (net (code "148") (name "Net-(C23-Pad1)") (class "Default")
      (node (ref "C23") (pin "1") (pinfunction "1_1") (pintype "passive"))
      (node (ref "R23") (pin "2") (pinfunction "2_2") (pintype "passive"))
      (node (ref "R24") (pin "1") (pinfunction "1_1") (pintype "passive"))
    )
    (net (code "149") (name "Net-(C25-Pad1)") (class "Default")
      (node (ref "C25") (pin "1") (pinfunction "1_1") (pintype "passive"))
      (node (ref "R25") (pin "2") (pinfunction "2_2") (pintype "passive"))
      (node (ref "R26") (pin "1") (pinfunction "1_1") (pintype "passive"))
    )
    (net (code "150") (name "Net-(C27-Pad1)") (class "Default")
      (node (ref "C27") (pin "1") (pinfunction "1_1") (pintype "passive"))
      (node (ref "R27") (pin "2") (pinfunction "2_2") (pintype "passive"))
      (node (ref "R28") (pin "1") (pinfunction "1_1") (pintype "passive"))
    )
    (net (code "151") (name "Net-(C29-Pad1)") (class "Default")
      (node (ref "C29") (pin "1") (pinfunction "1_1") (pintype "passive"))
      (node (ref "R29") (pin "2") (pinfunction "2_2") (pintype "passive"))
      (node (ref "R30") (pin "1") (pinfunction "1_1") (pintype "passive"))
    )
    (net (code "152") (name "Net-(C31-Pad1)") (class "Default")
      (node (ref "C31") (pin "1") (pinfunction "1_1") (pintype "passive"))
      (node (ref "R31") (pin "2") (pinfunction "2_2") (pintype "passive"))
      (node (ref "R32") (pin "1") (pinfunction "1_1") (pintype "passive"))
    )
    (net (code "153") (name "Net-(C33-Pad1)") (class "Default")
      (node (ref "C33") (pin "1") (pinfunction "1_1") (pintype "passive"))
      (node (ref "R33") (pin "2") (pinfunction "2_2") (pintype "passive"))
      (node (ref "R34") (pin "1") (pinfunction "1_1") (pintype "passive"))
    )
    (net (code "154") (name "Net-(C35-Pad1)") (class "Default")
      (node (ref "C35") (pin "1") (pinfunction "1_1") (pintype "passive"))
      (node (ref "R35") (pin "2") (pinfunction "2_2") (pintype "passive"))
      (node (ref "R36") (pin "1") (pinfunction "1_1") (pintype "passive"))
    )
    (net (code "155") (name "Net-(C37-Pad1)") (class "Default")
      (node (ref "C37") (pin "1") (pinfunction "1_1") (pintype "passive"))
      (node (ref "R37") (pin "2") (pinfunction "2_2") (pintype "passive"))
      (node (ref "R38") (pin "1") (pinfunction "1_1") (pintype "passive"))
    )
    (net (code "156") (name "Net-(C39-Pad1)") (class "Default")
      (node (ref "C39") (pin "1") (pinfunction "1_1") (pintype "passive"))
      (node (ref "R39") (pin "2") (pinfunction "2_2") (pintype "passive"))
      (node (ref "R40") (pin "1") (pinfunction "1_1") (pintype "passive"))
    )
    (net (code "157") (name "Net-(C41-Pad1)") (class "Default")
      (node (ref "C41") (pin "1") (pinfunction "1_1") (pintype "passive"))
      (node (ref "R41") (pin "2") (pinfunction "2_2") (pintype "passive"))
      (node (ref "R42") (pin "1") (pinfunction "1_1") (pintype "passive"))
    )
    (net (code "158") (name "Net-(C43-Pad1)") (class "Default")
      (node (ref "C43") (pin "1") (pinfunction "1_1") (pintype "passive"))
      (node (ref "R43") (pin "2") (pinfunction "2_2") (pintype "passive"))
      (node (ref "R44") (pin "1") (pinfunction "1_1") (pintype "passive"))
    )
    (net (code "159") (name "Net-(C45-Pad1)") (class "Default")
      (node (ref "C45") (pin "1") (pinfunction "1_1") (pintype "passive"))
      (node (ref "R45") (pin "2") (pinfunction "2_2") (pintype "passive"))
      (node (ref "R46") (pin "1") (pinfunction "1_1") (pintype "passive"))
    )
    (net (code "160") (name "Net-(C47-Pad1)") (class "Default")
      (node (ref "C47") (pin "1") (pinfunction "1_1") (pintype "passive"))
      (node (ref "R47") (pin "2") (pinfunction "2_2") (pintype "passive"))
      (node (ref "R48") (pin "1") (pinfunction "1_1") (pintype "passive"))
    )
    (net (code "161") (name "Net-(C49-Pad1)") (class "Default")
      (node (ref "C49") (pin "1") (pinfunction "1_1") (pintype "passive"))
      (node (ref "R49") (pin "2") (pinfunction "2_2") (pintype "passive"))
      (node (ref "R50") (pin "1") (pinfunction "1_1") (pintype "passive"))
    )
    (net (code "162") (name "Net-(C51-Pad1)") (class "Default")
      (node (ref "C51") (pin "1") (pinfunction "1_1") (pintype "passive"))
      (node (ref "R51") (pin "2") (pinfunction "2_2") (pintype "passive"))
      (node (ref "R52") (pin "1") (pinfunction "1_1") (pintype "passive"))
    )
    (net (code "163") (name "Net-(C53-Pad1)") (class "Default")
      (node (ref "C53") (pin "1") (pinfunction "1_1") (pintype "passive"))
      (node (ref "R53") (pin "2") (pinfunction "2_2") (pintype "passive"))
      (node (ref "R54") (pin "1") (pinfunction "1_1") (pintype "passive"))
    )
    (net (code "164") (name "Net-(C55-Pad1)") (class "Default")
      (node (ref "C55") (pin "1") (pinfunction "1_1") (pintype "passive"))
      (node (ref "R55") (pin "2") (pinfunction "2_2") (pintype "passive"))
      (node (ref "R56") (pin "1") (pinfunction "1_1") (pintype "passive"))
    )
    (net (code "165") (name "Net-(C57-Pad1)") (class "Default")
      (node (ref "C57") (pin "1") (pinfunction "1_1") (pintype "passive"))
      (node (ref "R57") (pin "2") (pinfunction "2_2") (pintype "passive"))
      (node (ref "R58") (pin "1") (pinfunction "1_1") (pintype "passive"))
    )
    (net (code "166") (name "Net-(C59-Pad1)") (class "Default")
      (node (ref "C59") (pin "1") (pinfunction "1_1") (pintype "passive"))
      (node (ref "R59") (pin "2") (pinfunction "2_2") (pintype "passive"))
      (node (ref "R60") (pin "1") (pinfunction "1_1") (pintype "passive"))
    )
    (net (code "167") (name "Net-(C61-Pad1)") (class "Default")
      (node (ref "C61") (pin "1") (pinfunction "1_1") (pintype "passive"))
      (node (ref "R61") (pin "2") (pinfunction "2_2") (pintype "passive"))
      (node (ref "R62") (pin "1") (pinfunction "1_1") (pintype "passive"))
    )
    (net (code "168") (name "Net-(C63-Pad1)") (class "Default")
      (node (ref "C63") (pin "1") (pinfunction "1_1") (pintype "passive"))
      (node (ref "R63") (pin "2") (pinfunction "2_2") (pintype "passive"))
      (node (ref "R64") (pin "1") (pinfunction "1_1") (pintype "passive"))
    )
    (net (code "169") (name "Net-(C65-Pad1)") (class "Default")
      (node (ref "C65") (pin "1") (pinfunction "1_1") (pintype "passive"))
      (node (ref "R65") (pin "2") (pinfunction "2_2") (pintype "passive"))
      (node (ref "R66") (pin "1") (pinfunction "1_1") (pintype "passive"))
    )
    (net (code "170") (name "Net-(C67-Pad1)") (class "Default")
      (node (ref "C67") (pin "1") (pinfunction "1_1") (pintype "passive"))
      (node (ref "R67") (pin "2") (pinfunction "2_2") (pintype "passive"))
      (node (ref "R68") (pin "1") (pinfunction "1_1") (pintype "passive"))
    )
    (net (code "171") (name "Net-(C69-Pad1)") (class "Default")
      (node (ref "C69") (pin "1") (pinfunction "1_1") (pintype "passive"))
      (node (ref "R69") (pin "2") (pinfunction "2_2") (pintype "passive"))
      (node (ref "R70") (pin "1") (pinfunction "1_1") (pintype "passive"))
    )
    (net (code "172") (name "Net-(C71-Pad1)") (class "Default")
      (node (ref "C71") (pin "1") (pinfunction "1_1") (pintype "passive"))
      (node (ref "R71") (pin "2") (pinfunction "2_2") (pintype "passive"))
      (node (ref "R72") (pin "1") (pinfunction "1_1") (pintype "passive"))
    )
    (net (code "173") (name "Net-(C73-Pad1)") (class "Default")
      (node (ref "C73") (pin "1") (pinfunction "1_1") (pintype "passive"))
      (node (ref "R73") (pin "2") (pinfunction "2_2") (pintype "passive"))
      (node (ref "R74") (pin "1") (pinfunction "1_1") (pintype "passive"))
    )
    (net (code "174") (name "Net-(C75-Pad1)") (class "Default")
      (node (ref "C75") (pin "1") (pinfunction "1_1") (pintype "passive"))
      (node (ref "R75") (pin "2") (pinfunction "2_2") (pintype "passive"))
      (node (ref "R76") (pin "1") (pinfunction "1_1") (pintype "passive"))
    )
    (net (code "175") (name "Net-(C77-Pad1)") (class "Default")
      (node (ref "C77") (pin "1") (pinfunction "1_1") (pintype "passive"))
      (node (ref "R77") (pin "2") (pinfunction "2_2") (pintype "passive"))
      (node (ref "R78") (pin "1") (pinfunction "1_1") (pintype "passive"))
    )
    (net (code "176") (name "Net-(C79-Pad1)") (class "Default")
      (node (ref "C79") (pin "1") (pinfunction "1_1") (pintype "passive"))
      (node (ref "R79") (pin "2") (pinfunction "2_2") (pintype "passive"))
      (node (ref "R80") (pin "1") (pinfunction "1_1") (pintype "passive"))
    )
    (net (code "177") (name "Net-(C81-Pad1)") (class "Default")
      (node (ref "C81") (pin "1") (pinfunction "1_1") (pintype "passive"))
      (node (ref "R81") (pin "2") (pinfunction "2_2") (pintype "passive"))
      (node (ref "R82") (pin "1") (pinfunction "1_1") (pintype "passive"))
    )
    (net (code "178") (name "Net-(C83-Pad1)") (class "Default")
      (node (ref "C83") (pin "1") (pinfunction "1_1") (pintype "passive"))
      (node (ref "R83") (pin "2") (pinfunction "2_2") (pintype "passive"))
      (node (ref "R84") (pin "1") (pinfunction "1_1") (pintype "passive"))
    )
    (net (code "179") (name "Net-(C85-Pad1)") (class "Default")
      (node (ref "C85") (pin "1") (pinfunction "1_1") (pintype "passive"))
      (node (ref "R85") (pin "2") (pinfunction "2_2") (pintype "passive"))
      (node (ref "R86") (pin "1") (pinfunction "1_1") (pintype "passive"))
    )
    (net (code "180") (name "Net-(C87-Pad1)") (class "Default")
      (node (ref "C87") (pin "1") (pinfunction "1_1") (pintype "passive"))
      (node (ref "R87") (pin "2") (pinfunction "2_2") (pintype "passive"))
      (node (ref "R88") (pin "1") (pinfunction "1_1") (pintype "passive"))
    )
    (net (code "181") (name "Net-(C89-Pad1)") (class "Default")
      (node (ref "C89") (pin "1") (pinfunction "1_1") (pintype "passive"))
      (node (ref "R89") (pin "2") (pinfunction "2_2") (pintype "passive"))
      (node (ref "R90") (pin "1") (pinfunction "1_1") (pintype "passive"))
    )
    (net (code "182") (name "Net-(C91-Pad1)") (class "Default")
      (node (ref "C91") (pin "1") (pinfunction "1_1") (pintype "passive"))
      (node (ref "R91") (pin "2") (pinfunction "2_2") (pintype "passive"))
      (node (ref "R92") (pin "1") (pinfunction "1_1") (pintype "passive"))
    )
    (net (code "183") (name "Net-(C93-Pad1)") (class "Default")
      (node (ref "C93") (pin "1") (pinfunction "1_1") (pintype "passive"))
      (node (ref "R93") (pin "2") (pinfunction "2_2") (pintype "passive"))
      (node (ref "R94") (pin "1") (pinfunction "1_1") (pintype "passive"))
    )
    (net (code "184") (name "Net-(C95-Pad1)") (class "Default")
      (node (ref "C95") (pin "1") (pinfunction "1_1") (pintype "passive"))
      (node (ref "R95") (pin "2") (pinfunction "2_2") (pintype "passive"))
      (node (ref "R96") (pin "1") (pinfunction "1_1") (pintype "passive"))
    )
    (net (code "185") (name "Net-(C97-Pad1)") (class "Default")
      (node (ref "C97") (pin "1") (pinfunction "1_1") (pintype "passive"))
      (node (ref "R97") (pin "2") (pinfunction "2_2") (pintype "passive"))
      (node (ref "R98") (pin "1") (pinfunction "1_1") (pintype "passive"))
    )
    (net (code "186") (name "Net-(C99-Pad1)") (class "Default")
      (node (ref "C99") (pin "1") (pinfunction "1_1") (pintype "passive"))
      (node (ref "R100") (pin "1") (pinfunction "1_1") (pintype "passive"))
      (node (ref "R99") (pin "2") (pinfunction "2_2") (pintype "passive"))
    )
    (net (code "187") (name "Net-(C101-Pad1)") (class "Default")
      (node (ref "C101") (pin "1") (pinfunction "1_1") (pintype "passive"))
      (node (ref "R101") (pin "2") (pinfunction "2_2") (pintype "passive"))
      (node (ref "R102") (pin "1") (pinfunction "1_1") (pintype "passive"))
    )
    (net (code "188") (name "Net-(C103-Pad1)") (class "Default")
      (node (ref "C103") (pin "1") (pinfunction "1_1") (pintype "passive"))
      (node (ref "R103") (pin "2") (pinfunction "2_2") (pintype "passive"))
      (node (ref "R104") (pin "1") (pinfunction "1_1") (pintype "passive"))
    )
    (net (code "189") (name "Net-(C105-Pad1)") (class "Default")
      (node (ref "C105") (pin "1") (pinfunction "1_1") (pintype "passive"))
      (node (ref "R105") (pin "2") (pinfunction "2_2") (pintype "passive"))
      (node (ref "R106") (pin "1") (pinfunction "1_1") (pintype "passive"))
    )
    (net (code "190") (name "Net-(C107-Pad1)") (class "Default")
      (node (ref "C107") (pin "1") (pinfunction "1_1") (pintype "passive"))
      (node (ref "R107") (pin "2") (pinfunction "2_2") (pintype "passive"))
      (node (ref "R108") (pin "1") (pinfunction "1_1") (pintype "passive"))
    )
    (net (code "191") (name "Net-(C109-Pad1)") (class "Default")
      (node (ref "C109") (pin "1") (pinfunction "1_1") (pintype "passive"))
      (node (ref "R109") (pin "2") (pinfunction "2_2") (pintype "passive"))
      (node (ref "R110") (pin "1") (pinfunction "1_1") (pintype "passive"))
    )
    (net (code "192") (name "Net-(C111-Pad1)") (class "Default")
      (node (ref "C111") (pin "1") (pinfunction "1_1") (pintype "passive"))
      (node (ref "R111") (pin "2") (pinfunction "2_2") (pintype "passive"))
      (node (ref "R112") (pin "1") (pinfunction "1_1") (pintype "passive"))
    )
    (net (code "193") (name "Net-(C113-Pad1)") (class "Default")
      (node (ref "C113") (pin "1") (pinfunction "1_1") (pintype "passive"))
      (node (ref "R113") (pin "2") (pinfunction "2_2") (pintype "passive"))
      (node (ref "R114") (pin "1") (pinfunction "1_1") (pintype "passive"))
    )
    (net (code "194") (name "Net-(C115-Pad1)") (class "Default")
      (node (ref "C115") (pin "1") (pinfunction "1_1") (pintype "passive"))
      (node (ref "R115") (pin "2") (pinfunction "2_2") (pintype "passive"))
      (node (ref "R116") (pin "1") (pinfunction "1_1") (pintype "passive"))
    )
    (net (code "195") (name "Net-(C117-Pad1)") (class "Default")
      (node (ref "C117") (pin "1") (pinfunction "1_1") (pintype "passive"))
      (node (ref "R117") (pin "2") (pinfunction "2_2") (pintype "passive"))
      (node (ref "R118") (pin "1") (pinfunction "1_1") (pintype "passive"))
    )
    (net (code "196") (name "Net-(C119-Pad1)") (class "Default")
      (node (ref "C119") (pin "1") (pinfunction "1_1") (pintype "passive"))
      (node (ref "R119") (pin "2") (pinfunction "2_2") (pintype "passive"))
      (node (ref "R120") (pin "1") (pinfunction "1_1") (pintype "passive"))
    )
    (net (code "197") (name "Net-(C121-Pad1)") (class "Default")
      (node (ref "C121") (pin "1") (pinfunction "1_1") (pintype "passive"))
      (node (ref "R121") (pin "2") (pinfunction "2_2") (pintype "passive"))
      (node (ref "R122") (pin "1") (pinfunction "1_1") (pintype "passive"))
    )
    (net (code "198") (name "Net-(C123-Pad1)") (class "Default")
      (node (ref "C123") (pin "1") (pinfunction "1_1") (pintype "passive"))
      (node (ref "R123") (pin "2") (pinfunction "2_2") (pintype "passive"))
      (node (ref "R124") (pin "1") (pinfunction "1_1") (pintype "passive"))
    )
    (net (code "199") (name "Net-(C125-Pad1)") (class "Default")
      (node (ref "C125") (pin "1") (pinfunction "1_1") (pintype "passive"))
      (node (ref "R125") (pin "2") (pinfunction "2_2") (pintype "passive"))
      (node (ref "R126") (pin "1") (pinfunction "1_1") (pintype "passive"))
    )
    (net (code "200") (name "Net-(C127-Pad1)") (class "Default")
      (node (ref "C127") (pin "1") (pinfunction "1_1") (pintype "passive"))
      (node (ref "R127") (pin "2") (pinfunction "2_2") (pintype "passive"))
      (node (ref "R128") (pin "1") (pinfunction "1_1") (pintype "passive"))
    )
    (net (code "201") (name "unconnected-(J1_1-32_IN-Pad2)") (class "Default")
      (node (ref "J1_1-32_IN") (pin "2") (pinfunction "2_2") (pintype "bidirectional"))
    )
    (net (code "202") (name "unconnected-(J1_1-32_IN-Pad9)") (class "Default")
      (node (ref "J1_1-32_IN") (pin "9") (pinfunction "9_9") (pintype "bidirectional"))
    )
    (net (code "203") (name "unconnected-(J1_1-32_IN-Pad20)") (class "Default")
      (node (ref "J1_1-32_IN") (pin "20") (pinfunction "20_20") (pintype "bidirectional"))
    )
    (net (code "204") (name "unconnected-(J1_1-32_IN-Pad27)") (class "Default")
      (node (ref "J1_1-32_IN") (pin "27") (pinfunction "27_27") (pintype "bidirectional"))
    )
    (net (code "205") (name "unconnected-(J1_1-32_IN-Pad37)") (class "Default")
      (node (ref "J1_1-32_IN") (pin "37") (pinfunction "37_37") (pintype "bidirectional"))
    )
    (net (code "206") (name "unconnected-(J1_1-32_IN-Pad38)") (class "Default")
      (node (ref "J1_1-32_IN") (pin "38") (pinfunction "38_38") (pintype "bidirectional"))
    )
    (net (code "207") (name "unconnected-(J1_1-32_IN-Pad39)") (class "Default")
      (node (ref "J1_1-32_IN") (pin "39") (pinfunction "39_39") (pintype "bidirectional"))
    )
    (net (code "208") (name "unconnected-(J1_1-32_IN-Pad40)") (class "Default")
      (node (ref "J1_1-32_IN") (pin "40") (pinfunction "40_40") (pintype "bidirectional"))
    )
    (net (code "209") (name "unconnected-(J2_33-64_IN-Pad2)") (class "Default")
      (node (ref "J2_33-64_IN") (pin "2") (pinfunction "2_2") (pintype "bidirectional"))
    )
    (net (code "210") (name "unconnected-(J2_33-64_IN-Pad9)") (class "Default")
      (node (ref "J2_33-64_IN") (pin "9") (pinfunction "9_9") (pintype "bidirectional"))
    )
    (net (code "211") (name "unconnected-(J2_33-64_IN-Pad20)") (class "Default")
      (node (ref "J2_33-64_IN") (pin "20") (pinfunction "20_20") (pintype "bidirectional"))
    )
    (net (code "212") (name "unconnected-(J2_33-64_IN-Pad27)") (class "Default")
      (node (ref "J2_33-64_IN") (pin "27") (pinfunction "27_27") (pintype "bidirectional"))
    )
    (net (code "213") (name "unconnected-(J2_33-64_IN-Pad37)") (class "Default")
      (node (ref "J2_33-64_IN") (pin "37") (pinfunction "37_37") (pintype "bidirectional"))
    )
    (net (code "214") (name "unconnected-(J2_33-64_IN-Pad38)") (class "Default")
      (node (ref "J2_33-64_IN") (pin "38") (pinfunction "38_38") (pintype "bidirectional"))
    )
    (net (code "215") (name "unconnected-(J2_33-64_IN-Pad39)") (class "Default")
      (node (ref "J2_33-64_IN") (pin "39") (pinfunction "39_39") (pintype "bidirectional"))
    )
    (net (code "216") (name "unconnected-(J2_33-64_IN-Pad40)") (class "Default")
      (node (ref "J2_33-64_IN") (pin "40") (pinfunction "40_40") (pintype "bidirectional"))
    )
    (net (code "217") (name "unconnected-(J3_REF_IN-Pad2)") (class "Default")
      (node (ref "J3_REF_IN") (pin "2") (pinfunction "2_2") (pintype "bidirectional"))
    )
    (net (code "218") (name "unconnected-(J3_REF_IN-Pad7)") (class "Default")
      (node (ref "J3_REF_IN") (pin "7") (pinfunction "7_7") (pintype "bidirectional"))
    )
    (net (code "219") (name "unconnected-(J3_REF_IN-Pad9)") (class "Default")
      (node (ref "J3_REF_IN") (pin "9") (pinfunction "9_9") (pintype "bidirectional"))
    )
    (net (code "220") (name "unconnected-(J3_REF_IN-Pad10)") (class "Default")
      (node (ref "J3_REF_IN") (pin "10") (pinfunction "10_10") (pintype "bidirectional"))
    )
    (net (code "221") (name "unconnected-(J3_REF_IN-Pad11)") (class "Default")
      (node (ref "J3_REF_IN") (pin "11") (pinfunction "11_11") (pintype "bidirectional"))
    )
    (net (code "222") (name "unconnected-(J3_REF_IN-Pad12)") (class "Default")
      (node (ref "J3_REF_IN") (pin "12") (pinfunction "12_12") (pintype "bidirectional"))
    )
    (net (code "223") (name "unconnected-(J3_REF_IN-Pad13)") (class "Default")
      (node (ref "J3_REF_IN") (pin "13") (pinfunction "13_13") (pintype "bidirectional"))
    )
    (net (code "224") (name "unconnected-(J3_REF_IN-Pad14)") (class "Default")
      (node (ref "J3_REF_IN") (pin "14") (pinfunction "14_14") (pintype "bidirectional"))
    )
    (net (code "225") (name "unconnected-(J3_REF_IN-Pad15)") (class "Default")
      (node (ref "J3_REF_IN") (pin "15") (pinfunction "15_15") (pintype "bidirectional"))
    )
    (net (code "226") (name "unconnected-(J3_REF_IN-Pad16)") (class "Default")
      (node (ref "J3_REF_IN") (pin "16") (pinfunction "16_16") (pintype "bidirectional"))
    )
    (net (code "227") (name "unconnected-(J3_REF_IN-Pad17)") (class "Default")
      (node (ref "J3_REF_IN") (pin "17") (pinfunction "17_17") (pintype "bidirectional"))
    )
    (net (code "228") (name "unconnected-(J3_REF_IN-Pad18)") (class "Default")
      (node (ref "J3_REF_IN") (pin "18") (pinfunction "18_18") (pintype "bidirectional"))
    )
    (net (code "229") (name "unconnected-(J3_REF_IN-Pad19)") (class "Default")
      (node (ref "J3_REF_IN") (pin "19") (pinfunction "19_19") (pintype "bidirectional"))
    )
    (net (code "230") (name "unconnected-(J3_REF_IN-Pad20)") (class "Default")
      (node (ref "J3_REF_IN") (pin "20") (pinfunction "20_20") (pintype "bidirectional"))
    )
    (net (code "231") (name "unconnected-(J3_REF_IN-Pad21)") (class "Default")
      (node (ref "J3_REF_IN") (pin "21") (pinfunction "21_21") (pintype "bidirectional"))
    )
    (net (code "232") (name "unconnected-(J3_REF_IN-Pad22)") (class "Default")
      (node (ref "J3_REF_IN") (pin "22") (pinfunction "22_22") (pintype "bidirectional"))
    )
    (net (code "233") (name "unconnected-(J3_REF_IN-Pad23)") (class "Default")
      (node (ref "J3_REF_IN") (pin "23") (pinfunction "23_23") (pintype "bidirectional"))
    )
    (net (code "234") (name "unconnected-(J3_REF_IN-Pad24)") (class "Default")
      (node (ref "J3_REF_IN") (pin "24") (pinfunction "24_24") (pintype "bidirectional"))
    )
    (net (code "235") (name "unconnected-(J3_REF_IN-Pad25)") (class "Default")
      (node (ref "J3_REF_IN") (pin "25") (pinfunction "25_25") (pintype "bidirectional"))
    )
    (net (code "236") (name "unconnected-(J3_REF_IN-Pad26)") (class "Default")
      (node (ref "J3_REF_IN") (pin "26") (pinfunction "26_26") (pintype "bidirectional"))
    )
    (net (code "237") (name "unconnected-(J3_REF_IN-Pad27)") (class "Default")
      (node (ref "J3_REF_IN") (pin "27") (pinfunction "27_27") (pintype "bidirectional"))
    )
    (net (code "238") (name "unconnected-(J3_REF_IN-Pad28)") (class "Default")
      (node (ref "J3_REF_IN") (pin "28") (pinfunction "28_28") (pintype "bidirectional"))
    )
    (net (code "239") (name "unconnected-(J3_REF_IN-Pad29)") (class "Default")
      (node (ref "J3_REF_IN") (pin "29") (pinfunction "29_29") (pintype "bidirectional"))
    )
    (net (code "240") (name "unconnected-(J3_REF_IN-Pad30)") (class "Default")
      (node (ref "J3_REF_IN") (pin "30") (pinfunction "30_30") (pintype "bidirectional"))
    )
    (net (code "241") (name "unconnected-(J3_REF_IN-Pad31)") (class "Default")
      (node (ref "J3_REF_IN") (pin "31") (pinfunction "31_31") (pintype "bidirectional"))
    )
    (net (code "242") (name "unconnected-(J3_REF_IN-Pad32)") (class "Default")
      (node (ref "J3_REF_IN") (pin "32") (pinfunction "32_32") (pintype "bidirectional"))
    )
    (net (code "243") (name "unconnected-(J3_REF_IN-Pad33)") (class "Default")
      (node (ref "J3_REF_IN") (pin "33") (pinfunction "33_33") (pintype "bidirectional"))
    )
    (net (code "244") (name "unconnected-(J3_REF_IN-Pad34)") (class "Default")
      (node (ref "J3_REF_IN") (pin "34") (pinfunction "34_34") (pintype "bidirectional"))
    )
    (net (code "245") (name "unconnected-(J3_REF_IN-Pad37)") (class "Default")
      (node (ref "J3_REF_IN") (pin "37") (pinfunction "37_37") (pintype "bidirectional"))
    )
    (net (code "246") (name "unconnected-(J3_REF_IN-Pad38)") (class "Default")
      (node (ref "J3_REF_IN") (pin "38") (pinfunction "38_38") (pintype "bidirectional"))
    )
    (net (code "247") (name "unconnected-(J3_REF_IN-Pad39)") (class "Default")
      (node (ref "J3_REF_IN") (pin "39") (pinfunction "39_39") (pintype "bidirectional"))
    )
    (net (code "248") (name "unconnected-(J3_REF_IN-Pad40)") (class "Default")
      (node (ref "J3_REF_IN") (pin "40") (pinfunction "40_40") (pintype "bidirectional"))
    )
    (net (code "249") (name "unconnected-(J4_1-32_OUT-Pad2)") (class "Default")
      (node (ref "J4_1-32_OUT") (pin "2") (pinfunction "2_2") (pintype "bidirectional"))
    )
    (net (code "250") (name "unconnected-(J4_1-32_OUT-Pad9)") (class "Default")
      (node (ref "J4_1-32_OUT") (pin "9") (pinfunction "9_9") (pintype "bidirectional"))
    )
    (net (code "251") (name "unconnected-(J4_1-32_OUT-Pad20)") (class "Default")
      (node (ref "J4_1-32_OUT") (pin "20") (pinfunction "20_20") (pintype "bidirectional"))
    )
    (net (code "252") (name "unconnected-(J4_1-32_OUT-Pad27)") (class "Default")
      (node (ref "J4_1-32_OUT") (pin "27") (pinfunction "27_27") (pintype "bidirectional"))
    )
    (net (code "253") (name "unconnected-(J4_1-32_OUT-Pad37)") (class "Default")
      (node (ref "J4_1-32_OUT") (pin "37") (pinfunction "37_37") (pintype "bidirectional"))
    )
    (net (code "254") (name "unconnected-(J4_1-32_OUT-Pad38)") (class "Default")
      (node (ref "J4_1-32_OUT") (pin "38") (pinfunction "38_38") (pintype "bidirectional"))
    )
    (net (code "255") (name "unconnected-(J4_1-32_OUT-Pad39)") (class "Default")
      (node (ref "J4_1-32_OUT") (pin "39") (pinfunction "39_39") (pintype "bidirectional"))
    )
    (net (code "256") (name "unconnected-(J4_1-32_OUT-Pad40)") (class "Default")
      (node (ref "J4_1-32_OUT") (pin "40") (pinfunction "40_40") (pintype "bidirectional"))
    )
    (net (code "257") (name "unconnected-(J5_33-64_OUT-Pad2)") (class "Default")
      (node (ref "J5_33-64_OUT") (pin "2") (pinfunction "2_2") (pintype "bidirectional"))
    )
    (net (code "258") (name "unconnected-(J5_33-64_OUT-Pad9)") (class "Default")
      (node (ref "J5_33-64_OUT") (pin "9") (pinfunction "9_9") (pintype "bidirectional"))
    )
    (net (code "259") (name "unconnected-(J5_33-64_OUT-Pad20)") (class "Default")
      (node (ref "J5_33-64_OUT") (pin "20") (pinfunction "20_20") (pintype "bidirectional"))
    )
    (net (code "260") (name "unconnected-(J5_33-64_OUT-Pad27)") (class "Default")
      (node (ref "J5_33-64_OUT") (pin "27") (pinfunction "27_27") (pintype "bidirectional"))
    )
    (net (code "261") (name "unconnected-(J5_33-64_OUT-Pad37)") (class "Default")
      (node (ref "J5_33-64_OUT") (pin "37") (pinfunction "37_37") (pintype "bidirectional"))
    )
    (net (code "262") (name "unconnected-(J5_33-64_OUT-Pad38)") (class "Default")
      (node (ref "J5_33-64_OUT") (pin "38") (pinfunction "38_38") (pintype "bidirectional"))
    )
    (net (code "263") (name "unconnected-(J5_33-64_OUT-Pad39)") (class "Default")
      (node (ref "J5_33-64_OUT") (pin "39") (pinfunction "39_39") (pintype "bidirectional"))
    )
    (net (code "264") (name "unconnected-(J5_33-64_OUT-Pad40)") (class "Default")
      (node (ref "J5_33-64_OUT") (pin "40") (pinfunction "40_40") (pintype "bidirectional"))
    )
    (net (code "265") (name "unconnected-(J6_REF_OUT-Pad2)") (class "Default")
      (node (ref "J6_REF_OUT") (pin "2") (pinfunction "2_2") (pintype "bidirectional"))
    )
    (net (code "266") (name "unconnected-(J6_REF_OUT-Pad7)") (class "Default")
      (node (ref "J6_REF_OUT") (pin "7") (pinfunction "7_7") (pintype "bidirectional"))
    )
    (net (code "267") (name "unconnected-(J6_REF_OUT-Pad9)") (class "Default")
      (node (ref "J6_REF_OUT") (pin "9") (pinfunction "9_9") (pintype "bidirectional"))
    )
    (net (code "268") (name "unconnected-(J6_REF_OUT-Pad10)") (class "Default")
      (node (ref "J6_REF_OUT") (pin "10") (pinfunction "10_10") (pintype "bidirectional"))
    )
    (net (code "269") (name "unconnected-(J6_REF_OUT-Pad11)") (class "Default")
      (node (ref "J6_REF_OUT") (pin "11") (pinfunction "11_11") (pintype "bidirectional"))
    )
    (net (code "270") (name "unconnected-(J6_REF_OUT-Pad12)") (class "Default")
      (node (ref "J6_REF_OUT") (pin "12") (pinfunction "12_12") (pintype "bidirectional"))
    )
    (net (code "271") (name "unconnected-(J6_REF_OUT-Pad13)") (class "Default")
      (node (ref "J6_REF_OUT") (pin "13") (pinfunction "13_13") (pintype "bidirectional"))
    )
    (net (code "272") (name "unconnected-(J6_REF_OUT-Pad14)") (class "Default")
      (node (ref "J6_REF_OUT") (pin "14") (pinfunction "14_14") (pintype "bidirectional"))
    )
    (net (code "273") (name "unconnected-(J6_REF_OUT-Pad15)") (class "Default")
      (node (ref "J6_REF_OUT") (pin "15") (pinfunction "15_15") (pintype "bidirectional"))
    )
    (net (code "274") (name "unconnected-(J6_REF_OUT-Pad16)") (class "Default")
      (node (ref "J6_REF_OUT") (pin "16") (pinfunction "16_16") (pintype "bidirectional"))
    )
    (net (code "275") (name "unconnected-(J6_REF_OUT-Pad17)") (class "Default")
      (node (ref "J6_REF_OUT") (pin "17") (pinfunction "17_17") (pintype "bidirectional"))
    )
    (net (code "276") (name "unconnected-(J6_REF_OUT-Pad18)") (class "Default")
      (node (ref "J6_REF_OUT") (pin "18") (pinfunction "18_18") (pintype "bidirectional"))
    )
    (net (code "277") (name "unconnected-(J6_REF_OUT-Pad19)") (class "Default")
      (node (ref "J6_REF_OUT") (pin "19") (pinfunction "19_19") (pintype "bidirectional"))
    )
    (net (code "278") (name "unconnected-(J6_REF_OUT-Pad20)") (class "Default")
      (node (ref "J6_REF_OUT") (pin "20") (pinfunction "20_20") (pintype "bidirectional"))
    )
    (net (code "279") (name "unconnected-(J6_REF_OUT-Pad21)") (class "Default")
      (node (ref "J6_REF_OUT") (pin "21") (pinfunction "21_21") (pintype "bidirectional"))
    )
    (net (code "280") (name "unconnected-(J6_REF_OUT-Pad22)") (class "Default")
      (node (ref "J6_REF_OUT") (pin "22") (pinfunction "22_22") (pintype "bidirectional"))
    )
    (net (code "281") (name "unconnected-(J6_REF_OUT-Pad23)") (class "Default")
      (node (ref "J6_REF_OUT") (pin "23") (pinfunction "23_23") (pintype "bidirectional"))
    )
    (net (code "282") (name "unconnected-(J6_REF_OUT-Pad24)") (class "Default")
      (node (ref "J6_REF_OUT") (pin "24") (pinfunction "24_24") (pintype "bidirectional"))
    )
    (net (code "283") (name "unconnected-(J6_REF_OUT-Pad25)") (class "Default")
      (node (ref "J6_REF_OUT") (pin "25") (pinfunction "25_25") (pintype "bidirectional"))
    )
    (net (code "284") (name "unconnected-(J6_REF_OUT-Pad26)") (class "Default")
      (node (ref "J6_REF_OUT") (pin "26") (pinfunction "26_26") (pintype "bidirectional"))
    )
    (net (code "285") (name "unconnected-(J6_REF_OUT-Pad27)") (class "Default")
      (node (ref "J6_REF_OUT") (pin "27") (pinfunction "27_27") (pintype "bidirectional"))
    )
    (net (code "286") (name "unconnected-(J6_REF_OUT-Pad28)") (class "Default")
      (node (ref "J6_REF_OUT") (pin "28") (pinfunction "28_28") (pintype "bidirectional"))
    )
    (net (code "287") (name "unconnected-(J6_REF_OUT-Pad29)") (class "Default")
      (node (ref "J6_REF_OUT") (pin "29") (pinfunction "29_29") (pintype "bidirectional"))
    )
    (net (code "288") (name "unconnected-(J6_REF_OUT-Pad30)") (class "Default")
      (node (ref "J6_REF_OUT") (pin "30") (pinfunction "30_30") (pintype "bidirectional"))
    )
    (net (code "289") (name "unconnected-(J6_REF_OUT-Pad31)") (class "Default")
      (node (ref "J6_REF_OUT") (pin "31") (pinfunction "31_31") (pintype "bidirectional"))
    )
    (net (code "290") (name "unconnected-(J6_REF_OUT-Pad32)") (class "Default")
      (node (ref "J6_REF_OUT") (pin "32") (pinfunction "32_32") (pintype "bidirectional"))
    )
    (net (code "291") (name "unconnected-(J6_REF_OUT-Pad33)") (class "Default")
      (node (ref "J6_REF_OUT") (pin "33") (pinfunction "33_33") (pintype "bidirectional"))
    )
    (net (code "292") (name "unconnected-(J6_REF_OUT-Pad34)") (class "Default")
      (node (ref "J6_REF_OUT") (pin "34") (pinfunction "34_34") (pintype "bidirectional"))
    )
    (net (code "293") (name "unconnected-(J6_REF_OUT-Pad37)") (class "Default")
      (node (ref "J6_REF_OUT") (pin "37") (pinfunction "37_37") (pintype "bidirectional"))
    )
    (net (code "294") (name "unconnected-(J6_REF_OUT-Pad38)") (class "Default")
      (node (ref "J6_REF_OUT") (pin "38") (pinfunction "38_38") (pintype "bidirectional"))
    )
    (net (code "295") (name "unconnected-(J6_REF_OUT-Pad39)") (class "Default")
      (node (ref "J6_REF_OUT") (pin "39") (pinfunction "39_39") (pintype "bidirectional"))
    )
    (net (code "296") (name "unconnected-(J6_REF_OUT-Pad40)") (class "Default")
      (node (ref "J6_REF_OUT") (pin "40") (pinfunction "40_40") (pintype "bidirectional"))
    )
  )
)
